# f429ig.net
KiCad netlist of a schematic drawn in Altium Designer
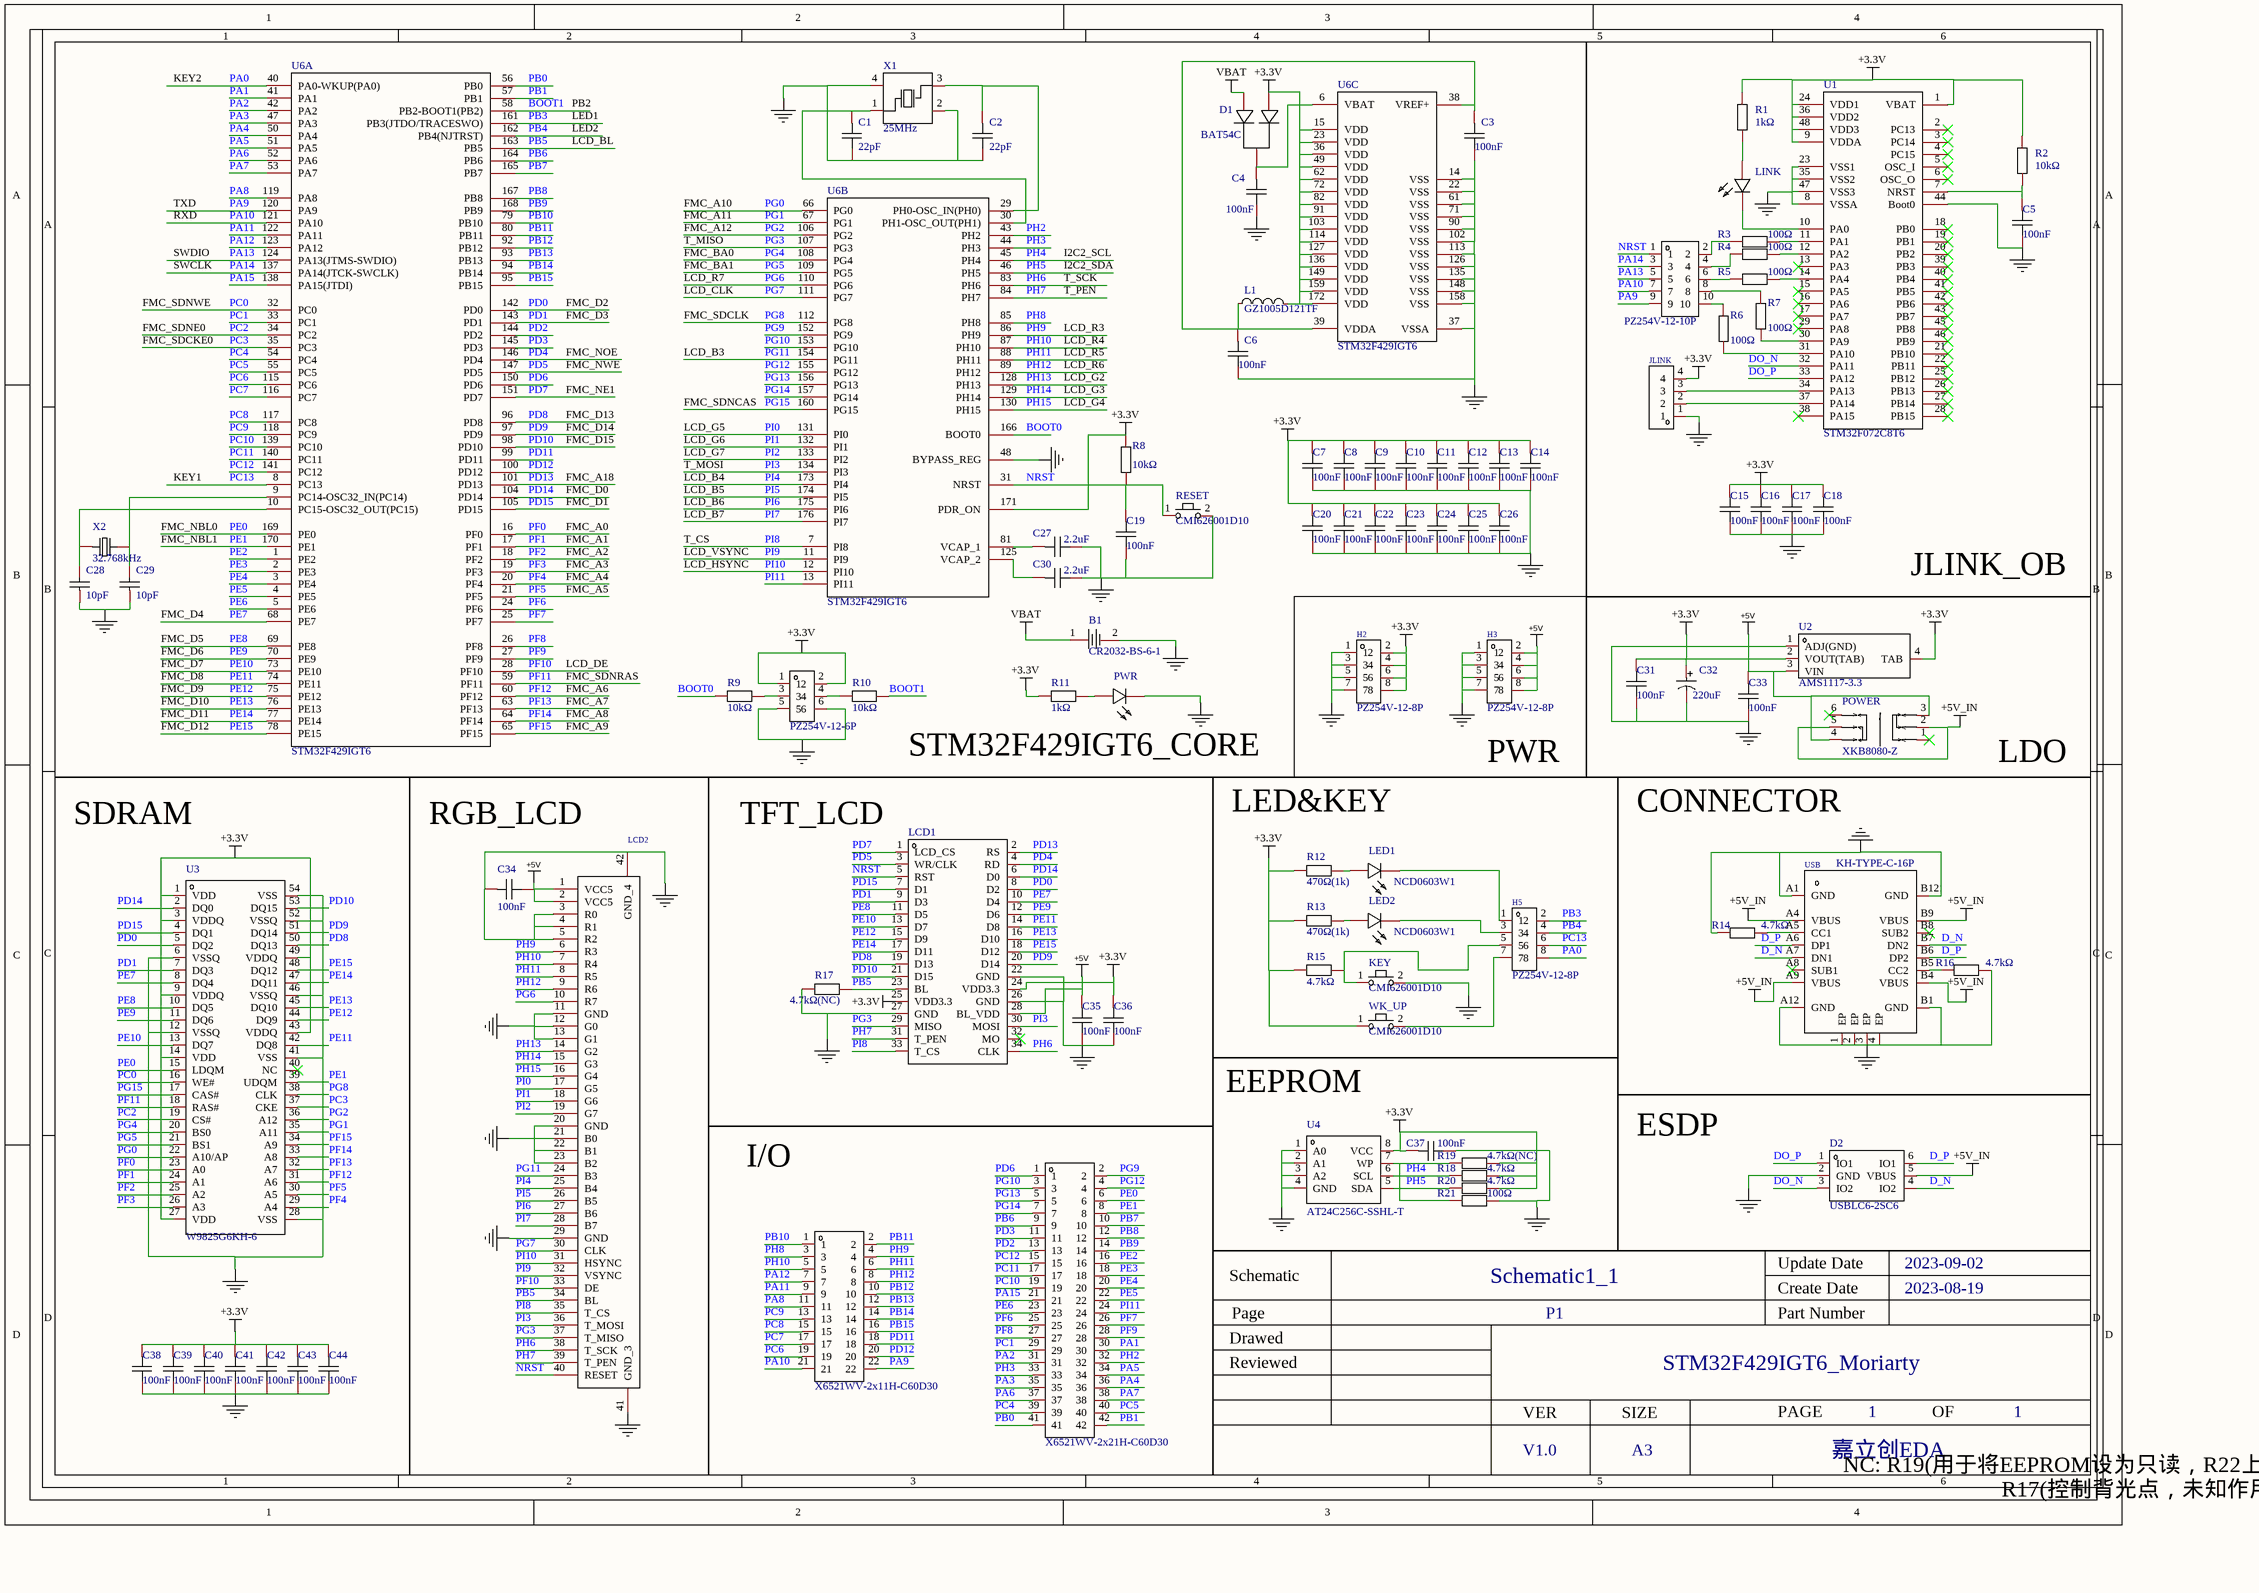
[diagram p0: f429ig.schdoc]

(export (version "E")
  (design (tool "Eeschema 10.0.6"))
  (components
    (comp (ref "B1")
      (value "CR2032-BS-6-1")
      (description "连接器类型:电池底座;适用电池规格:CR2032;工作温度范围:-;")
      (fields (field (name "NAME") "CR2032-BS-6-1") (field (name "MANUFACTURER") "QJ"))
      (libsource (lib "altium-import") (part "root_0_CR2032-BS-6-1_"))
    )
    (comp (ref "C1")
      (value "22pF")
      (description "温度系数:C0G;精度:±5%;额定电压:50V;容值:22pF;")
      (fields
        (field (name "NAME") "22pF")
        (field (name "MANUFACTURER") "FH(风华)")
        (field (name "MANUFACTURER PART") "0603CG220J500NT")
      )
      (libsource (lib "altium-import") (part "root_1_0603CG220J500NT_"))
    )
    (comp (ref "C2")
      (value "22pF")
      (description "温度系数:C0G;精度:±5%;额定电压:50V;容值:22pF;")
      (fields
        (field (name "NAME") "22pF")
        (field (name "MANUFACTURER") "FH(风华)")
        (field (name "MANUFACTURER PART") "0603CG220J500NT")
      )
      (libsource (lib "altium-import") (part "root_1_0603CG220J500NT_"))
    )
    (comp (ref "C3")
      (value "100nF")
      (fields (field (name "NAME") "100nF"))
      (libsource (lib "altium-import") (part "root_1_CAP_0603_"))
    )
    (comp (ref "C4")
      (value "100nF")
      (description "容值:100nF;精度:±10%;额定电压:50V;材质(温度系数):X7R;")
      (fields
        (field (name "NAME") "100nF")
        (field (name "MANUFACTURER") "YAGEO(国巨)")
        (field (name "MANUFACTURER PART") "CC0603KRX7R9BB104")
      )
      (libsource (lib "altium-import") (part "root_1_CC0603KRX7R9BB104_"))
    )
    (comp (ref "C5")
      (value "100nF")
      (description "容值:100nF;精度:±10%;额定电压:50V;材质(温度系数):X7R;")
      (fields
        (field (name "NAME") "100nF")
        (field (name "MANUFACTURER") "YAGEO(国巨)")
        (field (name "MANUFACTURER PART") "CC0603KRX7R9BB104")
      )
      (libsource (lib "altium-import") (part "root_1_CC0603KRX7R9BB104_"))
    )
    (comp (ref "C6")
      (value "100nF")
      (fields (field (name "NAME") "100nF"))
      (libsource (lib "altium-import") (part "root_1_CAP_0603_"))
    )
    (comp (ref "C7")
      (value "100nF")
      (description "容值:100nF;精度:±10%;额定电压:50V;材质(温度系数):X7R;")
      (fields
        (field (name "NAME") "100nF")
        (field (name "MANUFACTURER") "YAGEO(国巨)")
        (field (name "MANUFACTURER PART") "CC0603KRX7R9BB104")
      )
      (libsource (lib "altium-import") (part "root_1_CC0603KRX7R9BB104_"))
    )
    (comp (ref "C8")
      (value "100nF")
      (description "容值:100nF;精度:±10%;额定电压:50V;材质(温度系数):X7R;")
      (fields
        (field (name "NAME") "100nF")
        (field (name "MANUFACTURER") "YAGEO(国巨)")
        (field (name "MANUFACTURER PART") "CC0603KRX7R9BB104")
      )
      (libsource (lib "altium-import") (part "root_1_CC0603KRX7R9BB104_"))
    )
    (comp (ref "C9")
      (value "100nF")
      (description "容值:100nF;精度:±10%;额定电压:50V;材质(温度系数):X7R;")
      (fields
        (field (name "NAME") "100nF")
        (field (name "MANUFACTURER") "YAGEO(国巨)")
        (field (name "MANUFACTURER PART") "CC0603KRX7R9BB104")
      )
      (libsource (lib "altium-import") (part "root_1_CC0603KRX7R9BB104_"))
    )
    (comp (ref "C10")
      (value "100nF")
      (description "容值:100nF;精度:±10%;额定电压:50V;材质(温度系数):X7R;")
      (fields
        (field (name "NAME") "100nF")
        (field (name "MANUFACTURER") "YAGEO(国巨)")
        (field (name "MANUFACTURER PART") "CC0603KRX7R9BB104")
      )
      (libsource (lib "altium-import") (part "root_1_CC0603KRX7R9BB104_"))
    )
    (comp (ref "C11")
      (value "100nF")
      (description "容值:100nF;精度:±10%;额定电压:50V;材质(温度系数):X7R;")
      (fields
        (field (name "NAME") "100nF")
        (field (name "MANUFACTURER") "YAGEO(国巨)")
        (field (name "MANUFACTURER PART") "CC0603KRX7R9BB104")
      )
      (libsource (lib "altium-import") (part "root_1_CC0603KRX7R9BB104_"))
    )
    (comp (ref "C12")
      (value "100nF")
      (description "容值:100nF;精度:±10%;额定电压:50V;材质(温度系数):X7R;")
      (fields
        (field (name "NAME") "100nF")
        (field (name "MANUFACTURER") "YAGEO(国巨)")
        (field (name "MANUFACTURER PART") "CC0603KRX7R9BB104")
      )
      (libsource (lib "altium-import") (part "root_1_CC0603KRX7R9BB104_"))
    )
    (comp (ref "C13")
      (value "100nF")
      (description "容值:100nF;精度:±10%;额定电压:50V;材质(温度系数):X7R;")
      (fields
        (field (name "NAME") "100nF")
        (field (name "MANUFACTURER") "YAGEO(国巨)")
        (field (name "MANUFACTURER PART") "CC0603KRX7R9BB104")
      )
      (libsource (lib "altium-import") (part "root_1_CC0603KRX7R9BB104_"))
    )
    (comp (ref "C14")
      (value "100nF")
      (description "容值:100nF;精度:±10%;额定电压:50V;材质(温度系数):X7R;")
      (fields
        (field (name "NAME") "100nF")
        (field (name "MANUFACTURER") "YAGEO(国巨)")
        (field (name "MANUFACTURER PART") "CC0603KRX7R9BB104")
      )
      (libsource (lib "altium-import") (part "root_1_CC0603KRX7R9BB104_"))
    )
    (comp (ref "C15")
      (value "100nF")
      (description "容值:100nF;精度:±10%;额定电压:50V;材质(温度系数):X7R;")
      (fields
        (field (name "NAME") "100nF")
        (field (name "MANUFACTURER") "YAGEO(国巨)")
        (field (name "MANUFACTURER PART") "CC0603KRX7R9BB104")
      )
      (libsource (lib "altium-import") (part "root_1_CC0603KRX7R9BB104_"))
    )
    (comp (ref "C16")
      (value "100nF")
      (description "容值:100nF;精度:±10%;额定电压:50V;材质(温度系数):X7R;")
      (fields
        (field (name "NAME") "100nF")
        (field (name "MANUFACTURER") "YAGEO(国巨)")
        (field (name "MANUFACTURER PART") "CC0603KRX7R9BB104")
      )
      (libsource (lib "altium-import") (part "root_1_CC0603KRX7R9BB104_"))
    )
    (comp (ref "C17")
      (value "100nF")
      (description "容值:100nF;精度:±10%;额定电压:50V;材质(温度系数):X7R;")
      (fields
        (field (name "NAME") "100nF")
        (field (name "MANUFACTURER") "YAGEO(国巨)")
        (field (name "MANUFACTURER PART") "CC0603KRX7R9BB104")
      )
      (libsource (lib "altium-import") (part "root_1_CC0603KRX7R9BB104_"))
    )
    (comp (ref "C18")
      (value "100nF")
      (description "容值:100nF;精度:±10%;额定电压:50V;材质(温度系数):X7R;")
      (fields
        (field (name "NAME") "100nF")
        (field (name "MANUFACTURER") "YAGEO(国巨)")
        (field (name "MANUFACTURER PART") "CC0603KRX7R9BB104")
      )
      (libsource (lib "altium-import") (part "root_1_CC0603KRX7R9BB104_"))
    )
    (comp (ref "C19")
      (value "100nF")
      (description "容值:100nF;精度:±10%;额定电压:50V;材质(温度系数):X7R;")
      (fields
        (field (name "NAME") "100nF")
        (field (name "MANUFACTURER") "YAGEO(国巨)")
        (field (name "MANUFACTURER PART") "CC0603KRX7R9BB104")
      )
      (libsource (lib "altium-import") (part "root_1_CC0603KRX7R9BB104_"))
    )
    (comp (ref "C20")
      (value "100nF")
      (description "容值:100nF;精度:±10%;额定电压:50V;材质(温度系数):X7R;")
      (fields
        (field (name "NAME") "100nF")
        (field (name "MANUFACTURER") "YAGEO(国巨)")
        (field (name "MANUFACTURER PART") "CC0603KRX7R9BB104")
      )
      (libsource (lib "altium-import") (part "root_1_CC0603KRX7R9BB104_"))
    )
    (comp (ref "C21")
      (value "100nF")
      (description "容值:100nF;精度:±10%;额定电压:50V;材质(温度系数):X7R;")
      (fields
        (field (name "NAME") "100nF")
        (field (name "MANUFACTURER") "YAGEO(国巨)")
        (field (name "MANUFACTURER PART") "CC0603KRX7R9BB104")
      )
      (libsource (lib "altium-import") (part "root_1_CC0603KRX7R9BB104_"))
    )
    (comp (ref "C22")
      (value "100nF")
      (description "容值:100nF;精度:±10%;额定电压:50V;材质(温度系数):X7R;")
      (fields
        (field (name "NAME") "100nF")
        (field (name "MANUFACTURER") "YAGEO(国巨)")
        (field (name "MANUFACTURER PART") "CC0603KRX7R9BB104")
      )
      (libsource (lib "altium-import") (part "root_1_CC0603KRX7R9BB104_"))
    )
    (comp (ref "C23")
      (value "100nF")
      (description "容值:100nF;精度:±10%;额定电压:50V;材质(温度系数):X7R;")
      (fields
        (field (name "NAME") "100nF")
        (field (name "MANUFACTURER") "YAGEO(国巨)")
        (field (name "MANUFACTURER PART") "CC0603KRX7R9BB104")
      )
      (libsource (lib "altium-import") (part "root_1_CC0603KRX7R9BB104_"))
    )
    (comp (ref "C24")
      (value "100nF")
      (description "容值:100nF;精度:±10%;额定电压:50V;材质(温度系数):X7R;")
      (fields
        (field (name "NAME") "100nF")
        (field (name "MANUFACTURER") "YAGEO(国巨)")
        (field (name "MANUFACTURER PART") "CC0603KRX7R9BB104")
      )
      (libsource (lib "altium-import") (part "root_1_CC0603KRX7R9BB104_"))
    )
    (comp (ref "C25")
      (value "100nF")
      (description "容值:100nF;精度:±10%;额定电压:50V;材质(温度系数):X7R;")
      (fields
        (field (name "NAME") "100nF")
        (field (name "MANUFACTURER") "YAGEO(国巨)")
        (field (name "MANUFACTURER PART") "CC0603KRX7R9BB104")
      )
      (libsource (lib "altium-import") (part "root_1_CC0603KRX7R9BB104_"))
    )
    (comp (ref "C26")
      (value "100nF")
      (description "容值:100nF;精度:±10%;额定电压:50V;材质(温度系数):X7R;")
      (fields
        (field (name "NAME") "100nF")
        (field (name "MANUFACTURER") "YAGEO(国巨)")
        (field (name "MANUFACTURER PART") "CC0603KRX7R9BB104")
      )
      (libsource (lib "altium-import") (part "root_1_CC0603KRX7R9BB104_"))
    )
    (comp (ref "C27")
      (value "2.2uF")
      (description "容值:2.2uF;精度:±10%;额定电压:6.3V;材质(温度系数):X5R;")
      (fields
        (field (name "NAME") "2.2uF")
        (field (name "MANUFACTURER") "SAMSUNG(三星)")
        (field (name "MANUFACTURER PART") "CL10A225KQ8NNNC")
      )
      (libsource (lib "altium-import") (part "root_1_CL10A225KQ8NNNC_"))
    )
    (comp (ref "C28")
      (value "10pF")
      (description "容值:10pF;精度:±5%;额定电压:50V;材质(温度系数):NP0;")
      (fields
        (field (name "NAME") "10pF")
        (field (name "MANUFACTURER") "YAGEO(国巨)")
        (field (name "MANUFACTURER PART") "CC0603JRNPO9BN100")
      )
      (libsource (lib "altium-import") (part "root_1_CC0603JRNPO9BN100_"))
    )
    (comp (ref "C29")
      (value "10pF")
      (description "容值:10pF;精度:±5%;额定电压:50V;材质(温度系数):NP0;")
      (fields
        (field (name "NAME") "10pF")
        (field (name "MANUFACTURER") "YAGEO(国巨)")
        (field (name "MANUFACTURER PART") "CC0603JRNPO9BN100")
      )
      (libsource (lib "altium-import") (part "root_1_CC0603JRNPO9BN100_"))
    )
    (comp (ref "C30")
      (value "2.2uF")
      (description "容值:2.2uF;精度:±10%;额定电压:6.3V;材质(温度系数):X5R;")
      (fields
        (field (name "NAME") "2.2uF")
        (field (name "MANUFACTURER") "SAMSUNG(三星)")
        (field (name "MANUFACTURER PART") "CL10A225KQ8NNNC")
      )
      (libsource (lib "altium-import") (part "root_1_CL10A225KQ8NNNC_"))
    )
    (comp (ref "C31")
      (value "100nF")
      (description "容值:100nF;精度:±10%;额定电压:50V;材质(温度系数):X7R;")
      (fields
        (field (name "NAME") "100nF")
        (field (name "MANUFACTURER") "YAGEO(国巨)")
        (field (name "MANUFACTURER PART") "CC0603KRX7R9BB104")
      )
      (libsource (lib "altium-import") (part "root_1_CC0603KRX7R9BB104_"))
    )
    (comp (ref "C32")
      (value "220uF")
      (description "容值:220uF;精度:±20%;额定电压:10V;纹波电流:-;等效串联电阻:-;")
      (fields
        (field (name "NAME") "220uF")
        (field (name "MANUFACTURER") "ROQANG(容强)")
        (field (name "MANUFACTURER PART") "RVT1A221M0605")
      )
      (libsource (lib "altium-import") (part "root_0_RVT1A221M0605_C72494_"))
    )
    (comp (ref "C33")
      (value "100nF")
      (description "容值:100nF;精度:±10%;额定电压:50V;材质(温度系数):X7R;")
      (fields
        (field (name "NAME") "100nF")
        (field (name "MANUFACTURER") "YAGEO(国巨)")
        (field (name "MANUFACTURER PART") "CC0603KRX7R9BB104")
      )
      (libsource (lib "altium-import") (part "root_1_CC0603KRX7R9BB104_"))
    )
    (comp (ref "C34")
      (value "100nF")
      (description "容值:100nF;精度:±10%;额定电压:50V;材质(温度系数):X7R;")
      (fields
        (field (name "NAME") "100nF")
        (field (name "MANUFACTURER") "YAGEO(国巨)")
        (field (name "MANUFACTURER PART") "CC0603KRX7R9BB104")
      )
      (libsource (lib "altium-import") (part "root_2_CC0603KRX7R9BB104_"))
    )
    (comp (ref "C35")
      (value "100nF")
      (description "容值:100nF;精度:±10%;额定电压:50V;材质(温度系数):X7R;")
      (fields
        (field (name "NAME") "100nF")
        (field (name "MANUFACTURER") "YAGEO(国巨)")
        (field (name "MANUFACTURER PART") "CC0603KRX7R9BB104")
      )
      (libsource (lib "altium-import") (part "root_1_CC0603KRX7R9BB104_"))
    )
    (comp (ref "C36")
      (value "100nF")
      (description "容值:100nF;精度:±10%;额定电压:50V;材质(温度系数):X7R;")
      (fields
        (field (name "NAME") "100nF")
        (field (name "MANUFACTURER") "YAGEO(国巨)")
        (field (name "MANUFACTURER PART") "CC0603KRX7R9BB104")
      )
      (libsource (lib "altium-import") (part "root_1_CC0603KRX7R9BB104_"))
    )
    (comp (ref "C37")
      (value "100nF")
      (description "容值:100nF;精度:±10%;额定电压:50V;材质(温度系数):X7R;")
      (fields
        (field (name "NAME") "100nF")
        (field (name "MANUFACTURER") "YAGEO(国巨)")
        (field (name "MANUFACTURER PART") "CC0603KRX7R9BB104")
      )
      (libsource (lib "altium-import") (part "root_2_CC0603KRX7R9BB104_"))
    )
    (comp (ref "C38")
      (value "100nF")
      (description "容值:100nF;精度:±10%;额定电压:50V;材质(温度系数):X7R;")
      (fields
        (field (name "NAME") "100nF")
        (field (name "MANUFACTURER") "YAGEO(国巨)")
        (field (name "MANUFACTURER PART") "CC0603KRX7R9BB104")
      )
      (libsource (lib "altium-import") (part "root_1_CC0603KRX7R9BB104_"))
    )
    (comp (ref "C39")
      (value "100nF")
      (description "容值:100nF;精度:±10%;额定电压:50V;材质(温度系数):X7R;")
      (fields
        (field (name "NAME") "100nF")
        (field (name "MANUFACTURER") "YAGEO(国巨)")
        (field (name "MANUFACTURER PART") "CC0603KRX7R9BB104")
      )
      (libsource (lib "altium-import") (part "root_1_CC0603KRX7R9BB104_"))
    )
    (comp (ref "C40")
      (value "100nF")
      (description "容值:100nF;精度:±10%;额定电压:50V;材质(温度系数):X7R;")
      (fields
        (field (name "NAME") "100nF")
        (field (name "MANUFACTURER") "YAGEO(国巨)")
        (field (name "MANUFACTURER PART") "CC0603KRX7R9BB104")
      )
      (libsource (lib "altium-import") (part "root_1_CC0603KRX7R9BB104_"))
    )
    (comp (ref "C41")
      (value "100nF")
      (description "容值:100nF;精度:±10%;额定电压:50V;材质(温度系数):X7R;")
      (fields
        (field (name "NAME") "100nF")
        (field (name "MANUFACTURER") "YAGEO(国巨)")
        (field (name "MANUFACTURER PART") "CC0603KRX7R9BB104")
      )
      (libsource (lib "altium-import") (part "root_1_CC0603KRX7R9BB104_"))
    )
    (comp (ref "C42")
      (value "100nF")
      (description "容值:100nF;精度:±10%;额定电压:50V;材质(温度系数):X7R;")
      (fields
        (field (name "NAME") "100nF")
        (field (name "MANUFACTURER") "YAGEO(国巨)")
        (field (name "MANUFACTURER PART") "CC0603KRX7R9BB104")
      )
      (libsource (lib "altium-import") (part "root_1_CC0603KRX7R9BB104_"))
    )
    (comp (ref "C43")
      (value "100nF")
      (description "容值:100nF;精度:±10%;额定电压:50V;材质(温度系数):X7R;")
      (fields
        (field (name "NAME") "100nF")
        (field (name "MANUFACTURER") "YAGEO(国巨)")
        (field (name "MANUFACTURER PART") "CC0603KRX7R9BB104")
      )
      (libsource (lib "altium-import") (part "root_1_CC0603KRX7R9BB104_"))
    )
    (comp (ref "C44")
      (value "100nF")
      (description "容值:100nF;精度:±10%;额定电压:50V;材质(温度系数):X7R;")
      (fields
        (field (name "NAME") "100nF")
        (field (name "MANUFACTURER") "YAGEO(国巨)")
        (field (name "MANUFACTURER PART") "CC0603KRX7R9BB104")
      )
      (libsource (lib "altium-import") (part "root_1_CC0603KRX7R9BB104_"))
    )
    (comp (ref "D1")
      (value "BAT54C")
      (description "二极管配置:-;直流反向耐压(Vr):30V;平均整流电流(Io):200mA;正向压降(Vf):1V@100mA;")
      (fields (field (name "NAME") "BAT54C") (field (name "MANUFACTURER") "CJ(江苏长电/长晶)"))
      (libsource (lib "altium-import") (part "root_3_BAT54C_C2135_"))
    )
    (comp (ref "D2")
      (value "USBLC6-2SC6")
      (description "USBLC6-2SC6 Vrwm:5V 印记：UL26  ESD静电管静电放电(ESD)保护器件")
      (fields (field (name "NAME") "USBLC6-2SC6") (field (name "MANUFACTURER") "TECH PUBLIC(台舟)"))
      (libsource (lib "altium-import") (part "root_0_USBLC6-2SC6_C2827654_"))
    )
    (comp (ref "H1")
      (value "PZ254V-12-10P")
      (fields (field (name "NAME") "PZ254V-12-10P") (field (name "MANUFACTURER") "XFCN(兴飞)"))
      (libsource (lib "altium-import") (part "root_0_PZ254V-12-10P_"))
    )
    (comp (ref "H2")
      (value "PZ254V-12-8P")
      (fields (field (name "NAME") "PZ254V-12-8P") (field (name "MANUFACTURER") "XFCN(兴飞)"))
      (libsource (lib "altium-import") (part "root_0_PZ254V-12-8P_"))
    )
    (comp (ref "H3")
      (value "PZ254V-12-8P")
      (fields (field (name "NAME") "PZ254V-12-8P") (field (name "MANUFACTURER") "XFCN(兴飞)"))
      (libsource (lib "altium-import") (part "root_0_PZ254V-12-8P_"))
    )
    (comp (ref "H4")
      (value "PZ254V-12-6P")
      (fields (field (name "NAME") "PZ254V-12-6P") (field (name "MANUFACTURER") "XFCN(兴飞)"))
      (libsource (lib "altium-import") (part "root_0_PZ254V-12-6P_"))
    )
    (comp (ref "H5")
      (value "PZ254V-12-8P")
      (fields (field (name "NAME") "PZ254V-12-8P") (field (name "MANUFACTURER") "XFCN(兴飞)"))
      (libsource (lib "altium-import") (part "root_0_PZ254V-12-8P_"))
    )
    (comp (ref "H6")
      (value "X6521WV-2x11H-C60D30")
      (fields
        (field (name "NAME") "X6521WV-2x11H-C60D30")
        (field (name "MANUFACTURER") "XKB Connectivity(中国星坤)")
      )
      (libsource (lib "altium-import") (part "root_0_X6521WV-2x11H-C60D30_"))
    )
    (comp (ref "JLINK")
      (value "PZ254V-11-04P")
      (fields (field (name "MANUFACTURER") "XFCN(兴飞)"))
      (libsource (lib "altium-import") (part "root_2_PZ254V-11-04P_"))
    )
    (comp (ref "KEY")
      (value "CMI626001D10")
      (fields (field (name "NAME") "CMI626001D10") (field (name "MANUFACTURER") "Kailh(凯华)"))
      (libsource (lib "altium-import") (part "root_0_CMI626001D10_"))
    )
    (comp (ref "L1")
      (value "GZ1005D121TF")
      (description "标称阻抗@测试频率:120Ω@100MHz;误差:±25%;直流电阻(RDC):400mΩ;")
      (fields
        (field (name "NAME") "GZ1005D121TF")
        (field (name "MANUFACTURER") "Sunlord(顺络)")
        (field (name "TOLERANCE") "±25%")
      )
      (libsource (lib "altium-import") (part "root_0_GZ1005D121TF_"))
    )
    (comp (ref "LCD1") (value "~") (libsource (lib "altium-import") (part "root_0_PM2.54-2*17_")))
    (comp (ref "LCD2") (value "~") (libsource (lib "altium-import") (part "root_0_AFC01-S40FCA-00_")))
    (comp (ref "LED1")
      (value "NCD0603W1")
      (description "发光颜色:白灯;")
      (fields (field (name "NAME") "NCD0603W1") (field (name "MANUFACTURER") "国星光电"))
      (libsource (lib "altium-import") (part "root_2_NCD0603W1_"))
    )
    (comp (ref "LED2")
      (value "NCD0603W1")
      (description "发光颜色:白灯;")
      (fields (field (name "NAME") "NCD0603W1") (field (name "MANUFACTURER") "国星光电"))
      (libsource (lib "altium-import") (part "root_2_NCD0603W1_"))
    )
    (comp (ref "LINK")
      (value "NCD0603W1")
      (description "发光颜色:白灯;")
      (fields (field (name "MANUFACTURER") "国星光电"))
      (libsource (lib "altium-import") (part "root_1_NCD0603W1_"))
    )
    (comp (ref "POWER")
      (value "XKB8080-Z")
      (fields (field (name "NAME") "XKB8080-Z") (field (name "MANUFACTURER") "XKB Connectivity(中国星坤)"))
      (libsource (lib "altium-import") (part "root_1_XKB8080-Z_"))
    )
    (comp (ref "PWR")
      (value "NCD0603W1")
      (description "发光颜色:白灯;")
      (fields (field (name "MANUFACTURER") "国星光电"))
      (libsource (lib "altium-import") (part "root_2_NCD0603W1_"))
    )
    (comp (ref "R1")
      (value "1kΩ")
      (description "电阻类型:厚膜电阻;阻值:1kΩ;精度:±1%;功率:100mW;")
      (fields
        (field (name "NAME") "1kΩ")
        (field (name "MANUFACTURER") "UNI-ROYAL(厚声)")
        (field (name "MANUFACTURER PART") "0603WAF1001T5E")
      )
      (libsource (lib "altium-import") (part "root_1_0603WAF1001T5E_"))
    )
    (comp (ref "R2")
      (value "10kΩ")
      (description "电阻类型:厚膜电阻;阻值:10kΩ;精度:±1%;功率:100mW;")
      (fields
        (field (name "NAME") "10kΩ")
        (field (name "MANUFACTURER") "UNI-ROYAL(厚声)")
        (field (name "MANUFACTURER PART") "0603WAF1002T5E")
      )
      (libsource (lib "altium-import") (part "root_1_0603WAF1002T5E_"))
    )
    (comp (ref "R3")
      (value "100Ω")
      (description "电阻类型:厚膜电阻;阻值:100Ω;精度:±1%;功率:100mW;")
      (fields
        (field (name "NAME") "100Ω")
        (field (name "MANUFACTURER") "UNI-ROYAL(厚声)")
        (field (name "MANUFACTURER PART") "0603WAF1000T5E")
      )
      (libsource (lib "altium-import") (part "root_2_0603WAF1000T5E_"))
    )
    (comp (ref "R4")
      (value "100Ω")
      (description "电阻类型:厚膜电阻;阻值:100Ω;精度:±1%;功率:100mW;")
      (fields
        (field (name "NAME") "100Ω")
        (field (name "MANUFACTURER") "UNI-ROYAL(厚声)")
        (field (name "MANUFACTURER PART") "0603WAF1000T5E")
      )
      (libsource (lib "altium-import") (part "root_2_0603WAF1000T5E_"))
    )
    (comp (ref "R5")
      (value "100Ω")
      (description "电阻类型:厚膜电阻;阻值:100Ω;精度:±1%;功率:100mW;")
      (fields
        (field (name "NAME") "100Ω")
        (field (name "MANUFACTURER") "UNI-ROYAL(厚声)")
        (field (name "MANUFACTURER PART") "0603WAF1000T5E")
      )
      (libsource (lib "altium-import") (part "root_2_0603WAF1000T5E_"))
    )
    (comp (ref "R6")
      (value "100Ω")
      (description "电阻类型:厚膜电阻;阻值:100Ω;精度:±1%;功率:100mW;")
      (fields
        (field (name "NAME") "100Ω")
        (field (name "MANUFACTURER") "UNI-ROYAL(厚声)")
        (field (name "MANUFACTURER PART") "0603WAF1000T5E")
      )
      (libsource (lib "altium-import") (part "root_3_0603WAF1000T5E_"))
    )
    (comp (ref "R7")
      (value "100Ω")
      (description "电阻类型:厚膜电阻;阻值:100Ω;精度:±1%;功率:100mW;")
      (fields
        (field (name "NAME") "100Ω")
        (field (name "MANUFACTURER") "UNI-ROYAL(厚声)")
        (field (name "MANUFACTURER PART") "0603WAF1000T5E")
      )
      (libsource (lib "altium-import") (part "root_3_0603WAF1000T5E_"))
    )
    (comp (ref "R8")
      (value "10kΩ")
      (description "电阻类型:厚膜电阻;阻值:10kΩ;精度:±1%;功率:100mW;")
      (fields
        (field (name "NAME") "10kΩ")
        (field (name "MANUFACTURER") "UNI-ROYAL(厚声)")
        (field (name "MANUFACTURER PART") "0603WAF1002T5E")
      )
      (libsource (lib "altium-import") (part "root_1_0603WAF1002T5E_"))
    )
    (comp (ref "R9")
      (value "10kΩ")
      (description "电阻类型:厚膜电阻;阻值:10kΩ;精度:±1%;功率:100mW;")
      (fields
        (field (name "NAME") "10kΩ")
        (field (name "MANUFACTURER") "UNI-ROYAL(厚声)")
        (field (name "MANUFACTURER PART") "0603WAF1002T5E")
      )
      (libsource (lib "altium-import") (part "root_2_0603WAF1002T5E_"))
    )
    (comp (ref "R10")
      (value "10kΩ")
      (description "电阻类型:厚膜电阻;阻值:10kΩ;精度:±1%;功率:100mW;")
      (fields
        (field (name "NAME") "10kΩ")
        (field (name "MANUFACTURER") "UNI-ROYAL(厚声)")
        (field (name "MANUFACTURER PART") "0603WAF1002T5E")
      )
      (libsource (lib "altium-import") (part "root_2_0603WAF1002T5E_"))
    )
    (comp (ref "R11")
      (value "1kΩ")
      (description "电阻类型:厚膜电阻;阻值:1kΩ;精度:±1%;功率:100mW;")
      (fields
        (field (name "NAME") "1kΩ")
        (field (name "MANUFACTURER") "UNI-ROYAL(厚声)")
        (field (name "MANUFACTURER PART") "0603WAF1001T5E")
      )
      (libsource (lib "altium-import") (part "root_2_0603WAF1001T5E_"))
    )
    (comp (ref "R12")
      (value "470Ω(1k)")
      (description "电阻类型:厚膜电阻;阻值:470Ω;精度:±1%;功率:100mW;")
      (fields
        (field (name "NAME") "470Ω(1k)")
        (field (name "MANUFACTURER") "UNI-ROYAL(厚声)")
        (field (name "MANUFACTURER PART") "0603WAF4700T5E")
      )
      (libsource (lib "altium-import") (part "root_0_0603WAF4700T5E_"))
    )
    (comp (ref "R13")
      (value "470Ω(1k)")
      (description "电阻类型:厚膜电阻;阻值:470Ω;精度:±1%;功率:100mW;")
      (fields
        (field (name "NAME") "470Ω(1k)")
        (field (name "MANUFACTURER") "UNI-ROYAL(厚声)")
        (field (name "MANUFACTURER PART") "0603WAF4700T5E")
      )
      (libsource (lib "altium-import") (part "root_0_0603WAF4700T5E_"))
    )
    (comp (ref "R14")
      (value "4.7kΩ")
      (description "电阻类型:厚膜电阻;阻值:4.7kΩ;精度:±1%;功率:100mW;")
      (fields
        (field (name "NAME") "4.7kΩ")
        (field (name "MANUFACTURER") "UNI-ROYAL(厚声)")
        (field (name "MANUFACTURER PART") "0603WAF4701T5E")
      )
      (libsource (lib "altium-import") (part "root_2_0603WAF4701T5E_"))
    )
    (comp (ref "R15")
      (value "4.7kΩ")
      (description "电阻类型:厚膜电阻;阻值:4.7kΩ;精度:±1%;功率:100mW;")
      (fields
        (field (name "NAME") "4.7kΩ")
        (field (name "MANUFACTURER") "UNI-ROYAL(厚声)")
        (field (name "MANUFACTURER PART") "0603WAF4701T5E")
      )
      (libsource (lib "altium-import") (part "root_2_0603WAF4701T5E_"))
    )
    (comp (ref "R16")
      (value "4.7kΩ")
      (description "电阻类型:厚膜电阻;阻值:4.7kΩ;精度:±1%;功率:100mW;")
      (fields
        (field (name "NAME") "4.7kΩ")
        (field (name "MANUFACTURER") "UNI-ROYAL(厚声)")
        (field (name "MANUFACTURER PART") "0603WAF4701T5E")
      )
      (libsource (lib "altium-import") (part "root_2_0603WAF4701T5E_"))
    )
    (comp (ref "R17")
      (value "4.7kΩ(NC)")
      (description "电阻类型:厚膜电阻;阻值:4.7kΩ;精度:±1%;功率:100mW;")
      (fields
        (field (name "NAME") "4.7kΩ(NC)")
        (field (name "MANUFACTURER") "UNI-ROYAL(厚声)")
        (field (name "MANUFACTURER PART") "0603WAF4701T5E")
      )
      (libsource (lib "altium-import") (part "root_2_0603WAF4701T5E_"))
    )
    (comp (ref "R18")
      (value "4.7kΩ")
      (description "电阻类型:厚膜电阻;阻值:4.7kΩ;精度:±1%;功率:100mW;")
      (fields
        (field (name "NAME") "4.7kΩ")
        (field (name "MANUFACTURER") "UNI-ROYAL(厚声)")
        (field (name "MANUFACTURER PART") "0603WAF4701T5E")
      )
      (libsource (lib "altium-import") (part "root_2_0603WAF4701T5E_"))
    )
    (comp (ref "R19")
      (value "4.7kΩ(NC)")
      (description "电阻类型:厚膜电阻;阻值:4.7kΩ;精度:±1%;功率:100mW;")
      (fields
        (field (name "NAME") "4.7kΩ(NC)")
        (field (name "MANUFACTURER") "UNI-ROYAL(厚声)")
        (field (name "MANUFACTURER PART") "0603WAF4701T5E")
      )
      (libsource (lib "altium-import") (part "root_2_0603WAF4701T5E_"))
    )
    (comp (ref "R20")
      (value "4.7kΩ")
      (description "电阻类型:厚膜电阻;阻值:4.7kΩ;精度:±1%;功率:100mW;")
      (fields
        (field (name "NAME") "4.7kΩ")
        (field (name "MANUFACTURER") "UNI-ROYAL(厚声)")
        (field (name "MANUFACTURER PART") "0603WAF4701T5E")
      )
      (libsource (lib "altium-import") (part "root_2_0603WAF4701T5E_"))
    )
    (comp (ref "R21")
      (value "100Ω")
      (description "电阻类型:厚膜电阻;阻值:100Ω;精度:±1%;功率:100mW;")
      (fields
        (field (name "NAME") "100Ω")
        (field (name "MANUFACTURER") "UNI-ROYAL(厚声)")
        (field (name "MANUFACTURER PART") "0603WAF1000T5E")
      )
      (libsource (lib "altium-import") (part "root_2_0603WAF1000T5E_"))
    )
    (comp (ref "RESET")
      (value "CMI626001D10")
      (fields (field (name "NAME") "CMI626001D10") (field (name "MANUFACTURER") "Kailh(凯华)"))
      (libsource (lib "altium-import") (part "root_0_CMI626001D10_"))
    )
    (comp (ref "U1")
      (value "STM32F072C8T6")
      (fields (field (name "NAME") "STM32F072C8T6") (field (name "MANUFACTURER") "ST(意法半导体)"))
      (libsource (lib "altium-import") (part "root_0_STM32F072C8T6_"))
    )
    (comp (ref "U2")
      (value "AMS1117-3.3")
      (description "输出类型:固定;输出极性:正;最大输入电压:18V;输出电压:3.3V;输出电流:1A;电源纹波抑制比(PSRR):60dB@(120Hz);")
      (fields (field (name "NAME") "AMS1117-3.3") (field (name "MANUFACTURER") "UMW(广东友台半导体)"))
      (libsource (lib "altium-import") (part "root_0_AMS1117-3.3_C347222_"))
    )
    (comp (ref "U3")
      (value "W9825G6KH-6")
      (fields (field (name "NAME") "W9825G6KH-6") (field (name "MANUFACTURER") "WINBOND(华邦)"))
      (libsource (lib "altium-import") (part "root_0_W9825G6KH-6_"))
    )
    (comp (ref "U4")
      (value "AT24C256C-SSHL-T")
      (fields (field (name "NAME") "AT24C256C-SSHL-T") (field (name "MANUFACTURER") "MICROCHIP(美国微芯)"))
      (libsource (lib "altium-import") (part "root_0_AT24C256C-SSHL-T_"))
    )
    (comp (ref "U5")
      (value "X6521WV-2x21H-C60D30")
      (fields
        (field (name "NAME") "X6521WV-2x21H-C60D30")
        (field (name "MANUFACTURER") "XKB Connectivity(中国星坤)")
      )
      (libsource (lib "altium-import") (part "root_0_X6521WV-2x21H-C60D30_"))
    )
    (comp (ref "U6")
      (value "STM32F429IGT6")
      (description "CPU内核:ARM Cortex-M4;CPU最大主频:180MHz;程序存储容量:1MB;程序存储器类型:FLASH;RAM总容量:256KB;GPIO端口数量:140;")
      (fields (field (name "NAME") "STM32F429IGT6") (field (name "MANUFACTURER") "ST(意法半导体)"))
      (libsource (lib "altium-import") (part "root_0_STM32F429IGT6_"))
    )
    (comp (ref "USB")
      (value "KH-TYPE-C-16P")
      (description "Type-C母座 16PIN 立式四角贴板无压片")
      (fields (field (name "NAME") "KH-TYPE-C-16P") (field (name "MANUFACTURER") "kinghelm(金航标)"))
      (libsource (lib "altium-import") (part "root_0_KH-TYPE-C-16P_"))
    )
    (comp (ref "WK_UP")
      (value "CMI626001D10")
      (fields (field (name "NAME") "CMI626001D10") (field (name "MANUFACTURER") "Kailh(凯华)"))
      (libsource (lib "altium-import") (part "root_0_CMI626001D10_"))
    )
    (comp (ref "X1")
      (value "25MHz")
      (description "频率:25MHz;频率公差:±10ppm;负载电容:12pF;")
      (fields
        (field (name "NAME") "25MHz")
        (field (name "MANUFACTURER") "YXC(扬兴晶振)")
        (field (name "MANUFACTURER PART") "X322525MOB4SI")
      )
      (libsource (lib "altium-import") (part "root_0_X322525MOB4SI_"))
    )
    (comp (ref "X2")
      (value "32.768kHz")
      (description "频率:32.768kHz;频率公差:±20ppm;负载电容:6pF;")
      (fields
        (field (name "NAME") "32.768kHz")
        (field (name "MANUFACTURER") "EPSON(爱普生)")
        (field (name "MANUFACTURER PART") "Q13FC1350004900")
      )
      (libsource (lib "altium-import") (part "root_0_Q13FC1350004900_"))
    )
  )
  (nets
    (net (code "1") (name "+3.3V") (class "Default")
      (node (ref "C10") (pin "2") (pinfunction "2_2") (pintype "passive"))
      (node (ref "C11") (pin "2") (pinfunction "2_2") (pintype "passive"))
      (node (ref "C12") (pin "2") (pinfunction "2_2") (pintype "passive"))
      (node (ref "C13") (pin "2") (pinfunction "2_2") (pintype "passive"))
      (node (ref "C14") (pin "2") (pinfunction "2_2") (pintype "passive"))
      (node (ref "C15") (pin "2") (pinfunction "2_2") (pintype "passive"))
      (node (ref "C16") (pin "2") (pinfunction "2_2") (pintype "passive"))
      (node (ref "C17") (pin "2") (pinfunction "2_2") (pintype "passive"))
      (node (ref "C18") (pin "2") (pinfunction "2_2") (pintype "passive"))
      (node (ref "C20") (pin "2") (pinfunction "2_2") (pintype "passive"))
      (node (ref "C21") (pin "2") (pinfunction "2_2") (pintype "passive"))
      (node (ref "C22") (pin "2") (pinfunction "2_2") (pintype "passive"))
      (node (ref "C23") (pin "2") (pinfunction "2_2") (pintype "passive"))
      (node (ref "C24") (pin "2") (pinfunction "2_2") (pintype "passive"))
      (node (ref "C25") (pin "2") (pinfunction "2_2") (pintype "passive"))
      (node (ref "C26") (pin "2") (pinfunction "2_2") (pintype "passive"))
      (node (ref "C31") (pin "2") (pinfunction "2_2") (pintype "passive"))
      (node (ref "C32") (pin "1") (pinfunction "1_1") (pintype "passive"))
      (node (ref "C36") (pin "2") (pinfunction "2_2") (pintype "passive"))
      (node (ref "C37") (pin "2") (pinfunction "2_2") (pintype "passive"))
      (node (ref "C38") (pin "2") (pinfunction "2_2") (pintype "passive"))
      (node (ref "C39") (pin "2") (pinfunction "2_2") (pintype "passive"))
      (node (ref "C40") (pin "2") (pinfunction "2_2") (pintype "passive"))
      (node (ref "C41") (pin "2") (pinfunction "2_2") (pintype "passive"))
      (node (ref "C42") (pin "2") (pinfunction "2_2") (pintype "passive"))
      (node (ref "C43") (pin "2") (pinfunction "2_2") (pintype "passive"))
      (node (ref "C44") (pin "2") (pinfunction "2_2") (pintype "passive"))
      (node (ref "C7") (pin "2") (pinfunction "2_2") (pintype "passive"))
      (node (ref "C8") (pin "2") (pinfunction "2_2") (pintype "passive"))
      (node (ref "C9") (pin "2") (pinfunction "2_2") (pintype "passive"))
      (node (ref "D1") (pin "1") (pinfunction "A1_1") (pintype "passive"))
      (node (ref "H2") (pin "2") (pinfunction "2_2") (pintype "passive"))
      (node (ref "H2") (pin "4") (pinfunction "4_4") (pintype "passive"))
      (node (ref "H2") (pin "6") (pinfunction "6_6") (pintype "passive"))
      (node (ref "H2") (pin "8") (pinfunction "8_8") (pintype "passive"))
      (node (ref "H4") (pin "1") (pinfunction "1_1") (pintype "passive"))
      (node (ref "H4") (pin "2") (pinfunction "2_2") (pintype "passive"))
      (node (ref "JLINK") (pin "4") (pinfunction "4_4") (pintype "passive"))
      (node (ref "L1") (pin "2") (pinfunction "2_2") (pintype "passive"))
      (node (ref "LCD1") (pin "24") (pinfunction "VDD3.3_24") (pintype "passive"))
      (node (ref "LCD1") (pin "25") (pinfunction "VDD3.3_25") (pintype "passive"))
      (node (ref "R1") (pin "2") (pinfunction "2_2") (pintype "passive"))
      (node (ref "R11") (pin "2") (pinfunction "2_2") (pintype "passive"))
      (node (ref "R12") (pin "1") (pinfunction "1_1") (pintype "passive"))
      (node (ref "R13") (pin "1") (pinfunction "1_1") (pintype "passive"))
      (node (ref "R15") (pin "2") (pinfunction "2_2") (pintype "passive"))
      (node (ref "R18") (pin "1") (pinfunction "1_1") (pintype "passive"))
      (node (ref "R19") (pin "1") (pinfunction "1_1") (pintype "passive"))
      (node (ref "R2") (pin "2") (pinfunction "2_2") (pintype "passive"))
      (node (ref "R20") (pin "1") (pinfunction "1_1") (pintype "passive"))
      (node (ref "R8") (pin "2") (pinfunction "2_2") (pintype "passive"))
      (node (ref "U1") (pin "1") (pinfunction "VBAT_1") (pintype "passive"))
      (node (ref "U1") (pin "24") (pinfunction "VDD1_24") (pintype "passive"))
      (node (ref "U1") (pin "36") (pinfunction "VDD2_36") (pintype "passive"))
      (node (ref "U1") (pin "48") (pinfunction "VDD3_48") (pintype "passive"))
      (node (ref "U1") (pin "9") (pinfunction "VDDA_9") (pintype "passive"))
      (node (ref "U2") (pin "2") (pinfunction "VOUT(TAB)_2") (pintype "passive"))
      (node (ref "U2") (pin "4") (pinfunction "TAB_4") (pintype "passive"))
      (node (ref "U3") (pin "1") (pinfunction "VDD_1") (pintype "passive"))
      (node (ref "U3") (pin "14") (pinfunction "VDD_14") (pintype "passive"))
      (node (ref "U3") (pin "27") (pinfunction "VDD_27") (pintype "passive"))
      (node (ref "U3") (pin "3") (pinfunction "VDDQ_3") (pintype "passive"))
      (node (ref "U3") (pin "43") (pinfunction "VDDQ_43") (pintype "passive"))
      (node (ref "U3") (pin "49") (pinfunction "VDDQ_49") (pintype "passive"))
      (node (ref "U3") (pin "9") (pinfunction "VDDQ_9") (pintype "passive"))
      (node (ref "U4") (pin "8") (pinfunction "VCC_8") (pintype "passive"))
      (node (ref "U6") (pin "103") (pinfunction "VDD_103") (pintype "passive"))
      (node (ref "U6") (pin "114") (pinfunction "VDD_114") (pintype "passive"))
      (node (ref "U6") (pin "127") (pinfunction "VDD_127") (pintype "passive"))
      (node (ref "U6") (pin "136") (pinfunction "VDD_136") (pintype "passive"))
      (node (ref "U6") (pin "149") (pinfunction "VDD_149") (pintype "passive"))
      (node (ref "U6") (pin "15") (pinfunction "VDD_15") (pintype "passive"))
      (node (ref "U6") (pin "159") (pinfunction "VDD_159") (pintype "passive"))
      (node (ref "U6") (pin "171") (pinfunction "PDR_ON_171") (pintype "passive"))
      (node (ref "U6") (pin "172") (pinfunction "VDD_172") (pintype "passive"))
      (node (ref "U6") (pin "23") (pinfunction "VDD_23") (pintype "passive"))
      (node (ref "U6") (pin "36") (pinfunction "VDD_36") (pintype "passive"))
      (node (ref "U6") (pin "49") (pinfunction "VDD_49") (pintype "passive"))
      (node (ref "U6") (pin "62") (pinfunction "VDD_62") (pintype "passive"))
      (node (ref "U6") (pin "72") (pinfunction "VDD_72") (pintype "passive"))
      (node (ref "U6") (pin "82") (pinfunction "VDD_82") (pintype "passive"))
      (node (ref "U6") (pin "91") (pinfunction "VDD_91") (pintype "passive"))
      (node (ref "WK_UP") (pin "1") (pinfunction "1_1") (pintype "passive"))
    )
    (net (code "2") (name "+5V") (class "Default")
      (node (ref "C33") (pin "2") (pinfunction "2_2") (pintype "passive"))
      (node (ref "C34") (pin "1") (pinfunction "1_1") (pintype "passive"))
      (node (ref "C35") (pin "2") (pinfunction "2_2") (pintype "passive"))
      (node (ref "H3") (pin "2") (pinfunction "2_2") (pintype "passive"))
      (node (ref "H3") (pin "4") (pinfunction "4_4") (pintype "passive"))
      (node (ref "H3") (pin "6") (pinfunction "6_6") (pintype "passive"))
      (node (ref "H3") (pin "8") (pinfunction "8_8") (pintype "passive"))
      (node (ref "LCD1") (pin "28") (pinfunction "BL_VDD_28") (pintype "passive"))
      (node (ref "LCD2") (pin "1") (pinfunction "VCC5_1") (pintype "passive"))
      (node (ref "LCD2") (pin "2") (pinfunction "VCC5_2") (pintype "passive"))
      (node (ref "POWER") (pin "3") (pinfunction "3_3") (pintype "passive"))
      (node (ref "POWER") (pin "4") (pinfunction "4_4") (pintype "passive"))
      (node (ref "U2") (pin "3") (pinfunction "VIN_3") (pintype "passive"))
    )
    (net (code "3") (name "+5V_IN") (class "Default")
      (node (ref "D2") (pin "5") (pinfunction "VBUS_5") (pintype "passive"))
      (node (ref "POWER") (pin "2") (pinfunction "2_2") (pintype "passive"))
      (node (ref "POWER") (pin "5") (pinfunction "5_5") (pintype "passive"))
      (node (ref "USB") (pin "A4") (pinfunction "VBUS_A4") (pintype "passive"))
      (node (ref "USB") (pin "A9") (pinfunction "VBUS_A9") (pintype "passive"))
      (node (ref "USB") (pin "B4") (pinfunction "VBUS_B4") (pintype "passive"))
      (node (ref "USB") (pin "B9") (pinfunction "VBUS_B9") (pintype "passive"))
    )
    (net (code "4") (name "/BOOT0") (class "Default")
      (node (ref "R9") (pin "2") (pinfunction "2_2") (pintype "passive"))
      (node (ref "U6") (pin "166") (pinfunction "BOOT0_166") (pintype "passive"))
    )
    (net (code "5") (name "/BOOT1") (class "Default")
      (node (ref "R10") (pin "1") (pinfunction "1_1") (pintype "passive"))
      (node (ref "U6") (pin "58") (pinfunction "PB2-BOOT1(PB2)_58") (pintype "passive"))
    )
    (net (code "6") (name "/DO_N") (class "Default")
      (node (ref "D2") (pin "3") (pinfunction "IO2_3") (pintype "passive"))
      (node (ref "U1") (pin "32") (pinfunction "PA11_32") (pintype "passive"))
    )
    (net (code "7") (name "/DO_P") (class "Default")
      (node (ref "D2") (pin "1") (pinfunction "IO1_1") (pintype "passive"))
      (node (ref "U1") (pin "33") (pinfunction "PA12_33") (pintype "passive"))
    )
    (net (code "8") (name "/D_N") (class "Default")
      (node (ref "D2") (pin "4") (pinfunction "IO2_4") (pintype "passive"))
      (node (ref "USB") (pin "A7") (pinfunction "DN1_A7") (pintype "passive"))
      (node (ref "USB") (pin "B7") (pinfunction "DN2_B7") (pintype "passive"))
    )
    (net (code "9") (name "/D_P") (class "Default")
      (node (ref "D2") (pin "6") (pinfunction "IO1_6") (pintype "passive"))
      (node (ref "USB") (pin "A6") (pinfunction "DP1_A6") (pintype "passive"))
      (node (ref "USB") (pin "B6") (pinfunction "DP2_B6") (pintype "passive"))
    )
    (net (code "10") (name "/NRST") (class "Default")
      (node (ref "C19") (pin "2") (pinfunction "2_2") (pintype "passive"))
      (node (ref "H1") (pin "1") (pinfunction "1_1") (pintype "passive"))
      (node (ref "LCD1") (pin "5") (pinfunction "RST_5") (pintype "passive"))
      (node (ref "LCD2") (pin "40") (pinfunction "RESET_40") (pintype "passive"))
      (node (ref "R8") (pin "1") (pinfunction "1_1") (pintype "passive"))
      (node (ref "RESET") (pin "1") (pinfunction "1_1") (pintype "passive"))
      (node (ref "U6") (pin "31") (pinfunction "NRST_31") (pintype "passive"))
    )
    (net (code "11") (name "/PA0") (class "Default")
      (node (ref "H5") (pin "8") (pinfunction "8_8") (pintype "passive"))
      (node (ref "U6") (pin "40") (pinfunction "PA0-WKUP(PA0)_40") (pintype "passive"))
    )
    (net (code "12") (name "/PA1") (class "Default")
      (node (ref "U5") (pin "30") (pinfunction "30_30") (pintype "passive"))
      (node (ref "U6") (pin "41") (pinfunction "PA1_41") (pintype "passive"))
    )
    (net (code "13") (name "/PA2") (class "Default")
      (node (ref "U5") (pin "31") (pinfunction "31_31") (pintype "passive"))
      (node (ref "U6") (pin "42") (pinfunction "PA2_42") (pintype "passive"))
    )
    (net (code "14") (name "/PA3") (class "Default")
      (node (ref "U5") (pin "35") (pinfunction "35_35") (pintype "passive"))
      (node (ref "U6") (pin "47") (pinfunction "PA3_47") (pintype "passive"))
    )
    (net (code "15") (name "/PA4") (class "Default")
      (node (ref "U5") (pin "36") (pinfunction "36_36") (pintype "passive"))
      (node (ref "U6") (pin "50") (pinfunction "PA4_50") (pintype "passive"))
    )
    (net (code "16") (name "/PA5") (class "Default")
      (node (ref "U5") (pin "34") (pinfunction "34_34") (pintype "passive"))
      (node (ref "U6") (pin "51") (pinfunction "PA5_51") (pintype "passive"))
    )
    (net (code "17") (name "/PA6") (class "Default")
      (node (ref "U5") (pin "37") (pinfunction "37_37") (pintype "passive"))
      (node (ref "U6") (pin "52") (pinfunction "PA6_52") (pintype "passive"))
    )
    (net (code "18") (name "/PA7") (class "Default")
      (node (ref "U5") (pin "38") (pinfunction "38_38") (pintype "passive"))
      (node (ref "U6") (pin "53") (pinfunction "PA7_53") (pintype "passive"))
    )
    (net (code "19") (name "/PA8") (class "Default")
      (node (ref "H6") (pin "11") (pinfunction "11_11") (pintype "passive"))
      (node (ref "U6") (pin "119") (pinfunction "PA8_119") (pintype "passive"))
    )
    (net (code "20") (name "/PA9") (class "Default")
      (node (ref "H1") (pin "9") (pinfunction "9_9") (pintype "passive"))
      (node (ref "H6") (pin "22") (pinfunction "22_22") (pintype "passive"))
      (node (ref "U6") (pin "120") (pinfunction "PA9_120") (pintype "passive"))
    )
    (net (code "21") (name "/PA10") (class "Default")
      (node (ref "H1") (pin "7") (pinfunction "7_7") (pintype "passive"))
      (node (ref "H6") (pin "21") (pinfunction "21_21") (pintype "passive"))
      (node (ref "U6") (pin "121") (pinfunction "PA10_121") (pintype "passive"))
    )
    (net (code "22") (name "/PA11") (class "Default")
      (node (ref "H6") (pin "9") (pinfunction "9_9") (pintype "passive"))
      (node (ref "U6") (pin "122") (pinfunction "PA11_122") (pintype "passive"))
    )
    (net (code "23") (name "/PA12") (class "Default")
      (node (ref "H6") (pin "7") (pinfunction "7_7") (pintype "passive"))
      (node (ref "U6") (pin "123") (pinfunction "PA12_123") (pintype "passive"))
    )
    (net (code "24") (name "/PA13") (class "Default")
      (node (ref "H1") (pin "5") (pinfunction "5_5") (pintype "passive"))
      (node (ref "U6") (pin "124") (pinfunction "PA13(JTMS-SWDIO)_124") (pintype "passive"))
    )
    (net (code "25") (name "/PA14") (class "Default")
      (node (ref "H1") (pin "3") (pinfunction "3_3") (pintype "passive"))
      (node (ref "U6") (pin "137") (pinfunction "PA14(JTCK-SWCLK)_137") (pintype "passive"))
    )
    (net (code "26") (name "/PA15") (class "Default")
      (node (ref "U5") (pin "21") (pinfunction "21_21") (pintype "passive"))
      (node (ref "U6") (pin "138") (pinfunction "PA15(JTDI)_138") (pintype "passive"))
    )
    (net (code "27") (name "/PB0") (class "Default")
      (node (ref "U5") (pin "41") (pinfunction "41_41") (pintype "passive"))
      (node (ref "U6") (pin "56") (pinfunction "PB0_56") (pintype "passive"))
    )
    (net (code "28") (name "/PB1") (class "Default")
      (node (ref "U5") (pin "42") (pinfunction "42_42") (pintype "passive"))
      (node (ref "U6") (pin "57") (pinfunction "PB1_57") (pintype "passive"))
    )
    (net (code "29") (name "/PB3") (class "Default")
      (node (ref "H5") (pin "2") (pinfunction "2_2") (pintype "passive"))
      (node (ref "U6") (pin "161") (pinfunction "PB3(JTDO/TRACESWO)_161") (pintype "passive"))
    )
    (net (code "30") (name "/PB4") (class "Default")
      (node (ref "H5") (pin "4") (pinfunction "4_4") (pintype "passive"))
      (node (ref "U6") (pin "162") (pinfunction "PB4(NJTRST)_162") (pintype "passive"))
    )
    (net (code "31") (name "/PB5") (class "Default")
      (node (ref "LCD1") (pin "23") (pinfunction "BL_23") (pintype "passive"))
      (node (ref "LCD2") (pin "34") (pinfunction "BL_34") (pintype "passive"))
      (node (ref "R17") (pin "1") (pinfunction "1_1") (pintype "passive"))
      (node (ref "U6") (pin "163") (pinfunction "PB5_163") (pintype "passive"))
    )
    (net (code "32") (name "/PB6") (class "Default")
      (node (ref "U5") (pin "9") (pinfunction "9_9") (pintype "passive"))
      (node (ref "U6") (pin "164") (pinfunction "PB6_164") (pintype "passive"))
    )
    (net (code "33") (name "/PB7") (class "Default")
      (node (ref "U5") (pin "10") (pinfunction "10_10") (pintype "passive"))
      (node (ref "U6") (pin "165") (pinfunction "PB7_165") (pintype "passive"))
    )
    (net (code "34") (name "/PB8") (class "Default")
      (node (ref "U5") (pin "12") (pinfunction "12_12") (pintype "passive"))
      (node (ref "U6") (pin "167") (pinfunction "PB8_167") (pintype "passive"))
    )
    (net (code "35") (name "/PB9") (class "Default")
      (node (ref "U5") (pin "14") (pinfunction "14_14") (pintype "passive"))
      (node (ref "U6") (pin "168") (pinfunction "PB9_168") (pintype "passive"))
    )
    (net (code "36") (name "/PB10") (class "Default")
      (node (ref "H6") (pin "1") (pinfunction "1_1") (pintype "passive"))
      (node (ref "U6") (pin "79") (pinfunction "PB10_79") (pintype "passive"))
    )
    (net (code "37") (name "/PB11") (class "Default")
      (node (ref "H6") (pin "2") (pinfunction "2_2") (pintype "passive"))
      (node (ref "U6") (pin "80") (pinfunction "PB11_80") (pintype "passive"))
    )
    (net (code "38") (name "/PB12") (class "Default")
      (node (ref "H6") (pin "10") (pinfunction "10_10") (pintype "passive"))
      (node (ref "U6") (pin "92") (pinfunction "PB12_92") (pintype "passive"))
    )
    (net (code "39") (name "/PB13") (class "Default")
      (node (ref "H6") (pin "12") (pinfunction "12_12") (pintype "passive"))
      (node (ref "U6") (pin "93") (pinfunction "PB13_93") (pintype "passive"))
    )
    (net (code "40") (name "/PB14") (class "Default")
      (node (ref "H6") (pin "14") (pinfunction "14_14") (pintype "passive"))
      (node (ref "U6") (pin "94") (pinfunction "PB14_94") (pintype "passive"))
    )
    (net (code "41") (name "/PB15") (class "Default")
      (node (ref "H6") (pin "16") (pinfunction "16_16") (pintype "passive"))
      (node (ref "U6") (pin "95") (pinfunction "PB15_95") (pintype "passive"))
    )
    (net (code "42") (name "/PC0") (class "Default")
      (node (ref "U3") (pin "16") (pinfunction "WE#_16") (pintype "passive"))
      (node (ref "U6") (pin "32") (pinfunction "PC0_32") (pintype "passive"))
    )
    (net (code "43") (name "/PC1") (class "Default")
      (node (ref "U5") (pin "29") (pinfunction "29_29") (pintype "passive"))
      (node (ref "U6") (pin "33") (pinfunction "PC1_33") (pintype "passive"))
    )
    (net (code "44") (name "/PC2") (class "Default")
      (node (ref "U3") (pin "19") (pinfunction "CS#_19") (pintype "passive"))
      (node (ref "U6") (pin "34") (pinfunction "PC2_34") (pintype "passive"))
    )
    (net (code "45") (name "/PC3") (class "Default")
      (node (ref "U3") (pin "37") (pinfunction "CKE_37") (pintype "passive"))
      (node (ref "U6") (pin "35") (pinfunction "PC3_35") (pintype "passive"))
    )
    (net (code "46") (name "/PC4") (class "Default")
      (node (ref "U5") (pin "39") (pinfunction "39_39") (pintype "passive"))
      (node (ref "U6") (pin "54") (pinfunction "PC4_54") (pintype "passive"))
    )
    (net (code "47") (name "/PC5") (class "Default")
      (node (ref "U5") (pin "40") (pinfunction "40_40") (pintype "passive"))
      (node (ref "U6") (pin "55") (pinfunction "PC5_55") (pintype "passive"))
    )
    (net (code "48") (name "/PC6") (class "Default")
      (node (ref "H6") (pin "19") (pinfunction "19_19") (pintype "passive"))
      (node (ref "U6") (pin "115") (pinfunction "PC6_115") (pintype "passive"))
    )
    (net (code "49") (name "/PC7") (class "Default")
      (node (ref "H6") (pin "17") (pinfunction "17_17") (pintype "passive"))
      (node (ref "U6") (pin "116") (pinfunction "PC7_116") (pintype "passive"))
    )
    (net (code "50") (name "/PC8") (class "Default")
      (node (ref "H6") (pin "15") (pinfunction "15_15") (pintype "passive"))
      (node (ref "U6") (pin "117") (pinfunction "PC8_117") (pintype "passive"))
    )
    (net (code "51") (name "/PC9") (class "Default")
      (node (ref "H6") (pin "13") (pinfunction "13_13") (pintype "passive"))
      (node (ref "U6") (pin "118") (pinfunction "PC9_118") (pintype "passive"))
    )
    (net (code "52") (name "/PC10") (class "Default")
      (node (ref "U5") (pin "19") (pinfunction "19_19") (pintype "passive"))
      (node (ref "U6") (pin "139") (pinfunction "PC10_139") (pintype "passive"))
    )
    (net (code "53") (name "/PC11") (class "Default")
      (node (ref "U5") (pin "17") (pinfunction "17_17") (pintype "passive"))
      (node (ref "U6") (pin "140") (pinfunction "PC11_140") (pintype "passive"))
    )
    (net (code "54") (name "/PC12") (class "Default")
      (node (ref "U5") (pin "15") (pinfunction "15_15") (pintype "passive"))
      (node (ref "U6") (pin "141") (pinfunction "PC12_141") (pintype "passive"))
    )
    (net (code "55") (name "/PC13") (class "Default")
      (node (ref "H5") (pin "6") (pinfunction "6_6") (pintype "passive"))
      (node (ref "U6") (pin "8") (pinfunction "PC13_8") (pintype "passive"))
    )
    (net (code "56") (name "/PD0") (class "Default")
      (node (ref "LCD1") (pin "8") (pinfunction "D2_8") (pintype "passive"))
      (node (ref "U3") (pin "5") (pinfunction "DQ2_5") (pintype "passive"))
      (node (ref "U6") (pin "142") (pinfunction "PD0_142") (pintype "passive"))
    )
    (net (code "57") (name "/PD1") (class "Default")
      (node (ref "LCD1") (pin "9") (pinfunction "D3_9") (pintype "passive"))
      (node (ref "U3") (pin "7") (pinfunction "DQ3_7") (pintype "passive"))
      (node (ref "U6") (pin "143") (pinfunction "PD1_143") (pintype "passive"))
    )
    (net (code "58") (name "/PD2") (class "Default")
      (node (ref "U5") (pin "13") (pinfunction "13_13") (pintype "passive"))
      (node (ref "U6") (pin "144") (pinfunction "PD2_144") (pintype "passive"))
    )
    (net (code "59") (name "/PD3") (class "Default")
      (node (ref "U5") (pin "11") (pinfunction "11_11") (pintype "passive"))
      (node (ref "U6") (pin "145") (pinfunction "PD3_145") (pintype "passive"))
    )
    (net (code "60") (name "/PD4") (class "Default")
      (node (ref "LCD1") (pin "4") (pinfunction "RD_4") (pintype "passive"))
      (node (ref "U6") (pin "146") (pinfunction "PD4_146") (pintype "passive"))
    )
    (net (code "61") (name "/PD5") (class "Default")
      (node (ref "LCD1") (pin "3") (pinfunction "WR/CLK_3") (pintype "passive"))
      (node (ref "U6") (pin "147") (pinfunction "PD5_147") (pintype "passive"))
    )
    (net (code "62") (name "/PD6") (class "Default")
      (node (ref "U5") (pin "1") (pinfunction "1_1") (pintype "passive"))
      (node (ref "U6") (pin "150") (pinfunction "PD6_150") (pintype "passive"))
    )
    (net (code "63") (name "/PD7") (class "Default")
      (node (ref "LCD1") (pin "1") (pinfunction "LCD_CS_1") (pintype "passive"))
      (node (ref "U6") (pin "151") (pinfunction "PD7_151") (pintype "passive"))
    )
    (net (code "64") (name "/PD8") (class "Default")
      (node (ref "LCD1") (pin "19") (pinfunction "D13_19") (pintype "passive"))
      (node (ref "U3") (pin "50") (pinfunction "DQ13_50") (pintype "passive"))
      (node (ref "U6") (pin "96") (pinfunction "PD8_96") (pintype "passive"))
    )
    (net (code "65") (name "/PD9") (class "Default")
      (node (ref "LCD1") (pin "20") (pinfunction "D14_20") (pintype "passive"))
      (node (ref "U3") (pin "51") (pinfunction "DQ14_51") (pintype "passive"))
      (node (ref "U6") (pin "97") (pinfunction "PD9_97") (pintype "passive"))
    )
    (net (code "66") (name "/PD10") (class "Default")
      (node (ref "LCD1") (pin "21") (pinfunction "D15_21") (pintype "passive"))
      (node (ref "U3") (pin "53") (pinfunction "DQ15_53") (pintype "passive"))
      (node (ref "U6") (pin "98") (pinfunction "PD10_98") (pintype "passive"))
    )
    (net (code "67") (name "/PD11") (class "Default")
      (node (ref "H6") (pin "18") (pinfunction "18_18") (pintype "passive"))
      (node (ref "U6") (pin "99") (pinfunction "PD11_99") (pintype "passive"))
    )
    (net (code "68") (name "/PD12") (class "Default")
      (node (ref "H6") (pin "20") (pinfunction "20_20") (pintype "passive"))
      (node (ref "U6") (pin "100") (pinfunction "PD12_100") (pintype "passive"))
    )
    (net (code "69") (name "/PD13") (class "Default")
      (node (ref "LCD1") (pin "2") (pinfunction "RS_2") (pintype "passive"))
      (node (ref "U6") (pin "101") (pinfunction "PD13_101") (pintype "passive"))
    )
    (net (code "70") (name "/PD14") (class "Default")
      (node (ref "LCD1") (pin "6") (pinfunction "D0_6") (pintype "passive"))
      (node (ref "U3") (pin "2") (pinfunction "DQ0_2") (pintype "passive"))
      (node (ref "U6") (pin "104") (pinfunction "PD14_104") (pintype "passive"))
    )
    (net (code "71") (name "/PD15") (class "Default")
      (node (ref "LCD1") (pin "7") (pinfunction "D1_7") (pintype "passive"))
      (node (ref "U3") (pin "4") (pinfunction "DQ1_4") (pintype "passive"))
      (node (ref "U6") (pin "105") (pinfunction "PD15_105") (pintype "passive"))
    )
    (net (code "72") (name "/PE0") (class "Default")
      (node (ref "U3") (pin "15") (pinfunction "LDQM_15") (pintype "passive"))
      (node (ref "U5") (pin "6") (pinfunction "6_6") (pintype "passive"))
      (node (ref "U6") (pin "169") (pinfunction "PE0_169") (pintype "passive"))
    )
    (net (code "73") (name "/PE1") (class "Default")
      (node (ref "U3") (pin "39") (pinfunction "UDQM_39") (pintype "passive"))
      (node (ref "U5") (pin "8") (pinfunction "8_8") (pintype "passive"))
      (node (ref "U6") (pin "170") (pinfunction "PE1_170") (pintype "passive"))
    )
    (net (code "74") (name "/PE2") (class "Default")
      (node (ref "U5") (pin "16") (pinfunction "16_16") (pintype "passive"))
      (node (ref "U6") (pin "1") (pinfunction "PE2_1") (pintype "passive"))
    )
    (net (code "75") (name "/PE3") (class "Default")
      (node (ref "U5") (pin "18") (pinfunction "18_18") (pintype "passive"))
      (node (ref "U6") (pin "2") (pinfunction "PE3_2") (pintype "passive"))
    )
    (net (code "76") (name "/PE4") (class "Default")
      (node (ref "U5") (pin "20") (pinfunction "20_20") (pintype "passive"))
      (node (ref "U6") (pin "3") (pinfunction "PE4_3") (pintype "passive"))
    )
    (net (code "77") (name "/PE5") (class "Default")
      (node (ref "U5") (pin "22") (pinfunction "22_22") (pintype "passive"))
      (node (ref "U6") (pin "4") (pinfunction "PE5_4") (pintype "passive"))
    )
    (net (code "78") (name "/PE6") (class "Default")
      (node (ref "U5") (pin "23") (pinfunction "23_23") (pintype "passive"))
      (node (ref "U6") (pin "5") (pinfunction "PE6_5") (pintype "passive"))
    )
    (net (code "79") (name "/PE7") (class "Default")
      (node (ref "LCD1") (pin "10") (pinfunction "D4_10") (pintype "passive"))
      (node (ref "U3") (pin "8") (pinfunction "DQ4_8") (pintype "passive"))
      (node (ref "U6") (pin "68") (pinfunction "PE7_68") (pintype "passive"))
    )
    (net (code "80") (name "/PE8") (class "Default")
      (node (ref "LCD1") (pin "11") (pinfunction "D5_11") (pintype "passive"))
      (node (ref "U3") (pin "10") (pinfunction "DQ5_10") (pintype "passive"))
      (node (ref "U6") (pin "69") (pinfunction "PE8_69") (pintype "passive"))
    )
    (net (code "81") (name "/PE9") (class "Default")
      (node (ref "LCD1") (pin "12") (pinfunction "D6_12") (pintype "passive"))
      (node (ref "U3") (pin "11") (pinfunction "DQ6_11") (pintype "passive"))
      (node (ref "U6") (pin "70") (pinfunction "PE9_70") (pintype "passive"))
    )
    (net (code "82") (name "/PE10") (class "Default")
      (node (ref "LCD1") (pin "13") (pinfunction "D7_13") (pintype "passive"))
      (node (ref "U3") (pin "13") (pinfunction "DQ7_13") (pintype "passive"))
      (node (ref "U6") (pin "73") (pinfunction "PE10_73") (pintype "passive"))
    )
    (net (code "83") (name "/PE11") (class "Default")
      (node (ref "LCD1") (pin "14") (pinfunction "D8_14") (pintype "passive"))
      (node (ref "U3") (pin "42") (pinfunction "DQ8_42") (pintype "passive"))
      (node (ref "U6") (pin "74") (pinfunction "PE11_74") (pintype "passive"))
    )
    (net (code "84") (name "/PE12") (class "Default")
      (node (ref "LCD1") (pin "15") (pinfunction "D9_15") (pintype "passive"))
      (node (ref "U3") (pin "44") (pinfunction "DQ9_44") (pintype "passive"))
      (node (ref "U6") (pin "75") (pinfunction "PE12_75") (pintype "passive"))
    )
    (net (code "85") (name "/PE13") (class "Default")
      (node (ref "LCD1") (pin "16") (pinfunction "D10_16") (pintype "passive"))
      (node (ref "U3") (pin "45") (pinfunction "DQ10_45") (pintype "passive"))
      (node (ref "U6") (pin "76") (pinfunction "PE13_76") (pintype "passive"))
    )
    (net (code "86") (name "/PE14") (class "Default")
      (node (ref "LCD1") (pin "17") (pinfunction "D11_17") (pintype "passive"))
      (node (ref "U3") (pin "47") (pinfunction "DQ11_47") (pintype "passive"))
      (node (ref "U6") (pin "77") (pinfunction "PE14_77") (pintype "passive"))
    )
    (net (code "87") (name "/PE15") (class "Default")
      (node (ref "LCD1") (pin "18") (pinfunction "D12_18") (pintype "passive"))
      (node (ref "U3") (pin "48") (pinfunction "DQ12_48") (pintype "passive"))
      (node (ref "U6") (pin "78") (pinfunction "PE15_78") (pintype "passive"))
    )
    (net (code "88") (name "/PF0") (class "Default")
      (node (ref "U3") (pin "23") (pinfunction "A0_23") (pintype "passive"))
      (node (ref "U6") (pin "16") (pinfunction "PF0_16") (pintype "passive"))
    )
    (net (code "89") (name "/PF1") (class "Default")
      (node (ref "U3") (pin "24") (pinfunction "A1_24") (pintype "passive"))
      (node (ref "U6") (pin "17") (pinfunction "PF1_17") (pintype "passive"))
    )
    (net (code "90") (name "/PF2") (class "Default")
      (node (ref "U3") (pin "25") (pinfunction "A2_25") (pintype "passive"))
      (node (ref "U6") (pin "18") (pinfunction "PF2_18") (pintype "passive"))
    )
    (net (code "91") (name "/PF3") (class "Default")
      (node (ref "U3") (pin "26") (pinfunction "A3_26") (pintype "passive"))
      (node (ref "U6") (pin "19") (pinfunction "PF3_19") (pintype "passive"))
    )
    (net (code "92") (name "/PF4") (class "Default")
      (node (ref "U3") (pin "29") (pinfunction "A4_29") (pintype "passive"))
      (node (ref "U6") (pin "20") (pinfunction "PF4_20") (pintype "passive"))
    )
    (net (code "93") (name "/PF5") (class "Default")
      (node (ref "U3") (pin "30") (pinfunction "A5_30") (pintype "passive"))
      (node (ref "U6") (pin "21") (pinfunction "PF5_21") (pintype "passive"))
    )
    (net (code "94") (name "/PF6") (class "Default")
      (node (ref "U5") (pin "25") (pinfunction "25_25") (pintype "passive"))
      (node (ref "U6") (pin "24") (pinfunction "PF6_24") (pintype "passive"))
    )
    (net (code "95") (name "/PF7") (class "Default")
      (node (ref "U5") (pin "26") (pinfunction "26_26") (pintype "passive"))
      (node (ref "U6") (pin "25") (pinfunction "PF7_25") (pintype "passive"))
    )
    (net (code "96") (name "/PF8") (class "Default")
      (node (ref "U5") (pin "27") (pinfunction "27_27") (pintype "passive"))
      (node (ref "U6") (pin "26") (pinfunction "PF8_26") (pintype "passive"))
    )
    (net (code "97") (name "/PF9") (class "Default")
      (node (ref "U5") (pin "28") (pinfunction "28_28") (pintype "passive"))
      (node (ref "U6") (pin "27") (pinfunction "PF9_27") (pintype "passive"))
    )
    (net (code "98") (name "/PF10") (class "Default")
      (node (ref "LCD2") (pin "33") (pinfunction "DE_33") (pintype "passive"))
      (node (ref "U6") (pin "28") (pinfunction "PF10_28") (pintype "passive"))
    )
    (net (code "99") (name "/PF11") (class "Default")
      (node (ref "U3") (pin "18") (pinfunction "RAS#_18") (pintype "passive"))
      (node (ref "U6") (pin "59") (pinfunction "PF11_59") (pintype "passive"))
    )
    (net (code "100") (name "/PF12") (class "Default")
      (node (ref "U3") (pin "31") (pinfunction "A6_31") (pintype "passive"))
      (node (ref "U6") (pin "60") (pinfunction "PF12_60") (pintype "passive"))
    )
    (net (code "101") (name "/PF13") (class "Default")
      (node (ref "U3") (pin "32") (pinfunction "A7_32") (pintype "passive"))
      (node (ref "U6") (pin "63") (pinfunction "PF13_63") (pintype "passive"))
    )
    (net (code "102") (name "/PF14") (class "Default")
      (node (ref "U3") (pin "33") (pinfunction "A8_33") (pintype "passive"))
      (node (ref "U6") (pin "64") (pinfunction "PF14_64") (pintype "passive"))
    )
    (net (code "103") (name "/PF15") (class "Default")
      (node (ref "U3") (pin "34") (pinfunction "A9_34") (pintype "passive"))
      (node (ref "U6") (pin "65") (pinfunction "PF15_65") (pintype "passive"))
    )
    (net (code "104") (name "/PG0") (class "Default")
      (node (ref "U3") (pin "22") (pinfunction "A10/AP_22") (pintype "passive"))
      (node (ref "U6") (pin "66") (pinfunction "PG0_66") (pintype "passive"))
    )
    (net (code "105") (name "/PG1") (class "Default")
      (node (ref "U3") (pin "35") (pinfunction "A11_35") (pintype "passive"))
      (node (ref "U6") (pin "67") (pinfunction "PG1_67") (pintype "passive"))
    )
    (net (code "106") (name "/PG2") (class "Default")
      (node (ref "U3") (pin "36") (pinfunction "A12_36") (pintype "passive"))
      (node (ref "U6") (pin "106") (pinfunction "PG2_106") (pintype "passive"))
    )
    (net (code "107") (name "/PG3") (class "Default")
      (node (ref "LCD1") (pin "29") (pinfunction "MISO_29") (pintype "passive"))
      (node (ref "LCD2") (pin "37") (pinfunction "T_MISO_37") (pintype "passive"))
      (node (ref "U6") (pin "107") (pinfunction "PG3_107") (pintype "passive"))
    )
    (net (code "108") (name "/PG4") (class "Default")
      (node (ref "U3") (pin "20") (pinfunction "BS0_20") (pintype "passive"))
      (node (ref "U6") (pin "108") (pinfunction "PG4_108") (pintype "passive"))
    )
    (net (code "109") (name "/PG5") (class "Default")
      (node (ref "U3") (pin "21") (pinfunction "BS1_21") (pintype "passive"))
      (node (ref "U6") (pin "109") (pinfunction "PG5_109") (pintype "passive"))
    )
    (net (code "110") (name "/PG6") (class "Default")
      (node (ref "LCD2") (pin "10") (pinfunction "R7_10") (pintype "passive"))
      (node (ref "U6") (pin "110") (pinfunction "PG6_110") (pintype "passive"))
    )
    (net (code "111") (name "/PG7") (class "Default")
      (node (ref "LCD2") (pin "30") (pinfunction "CLK_30") (pintype "passive"))
      (node (ref "U6") (pin "111") (pinfunction "PG7_111") (pintype "passive"))
    )
    (net (code "112") (name "/PG8") (class "Default")
      (node (ref "U3") (pin "38") (pinfunction "CLK_38") (pintype "passive"))
      (node (ref "U6") (pin "112") (pinfunction "PG8_112") (pintype "passive"))
    )
    (net (code "113") (name "/PG9") (class "Default")
      (node (ref "U5") (pin "2") (pinfunction "2_2") (pintype "passive"))
      (node (ref "U6") (pin "152") (pinfunction "PG9_152") (pintype "passive"))
    )
    (net (code "114") (name "/PG10") (class "Default")
      (node (ref "U5") (pin "3") (pinfunction "3_3") (pintype "passive"))
      (node (ref "U6") (pin "153") (pinfunction "PG10_153") (pintype "passive"))
    )
    (net (code "115") (name "/PG11") (class "Default")
      (node (ref "LCD2") (pin "24") (pinfunction "B3_24") (pintype "passive"))
      (node (ref "U6") (pin "154") (pinfunction "PG11_154") (pintype "passive"))
    )
    (net (code "116") (name "/PG12") (class "Default")
      (node (ref "U5") (pin "4") (pinfunction "4_4") (pintype "passive"))
      (node (ref "U6") (pin "155") (pinfunction "PG12_155") (pintype "passive"))
    )
    (net (code "117") (name "/PG13") (class "Default")
      (node (ref "U5") (pin "5") (pinfunction "5_5") (pintype "passive"))
      (node (ref "U6") (pin "156") (pinfunction "PG13_156") (pintype "passive"))
    )
    (net (code "118") (name "/PG14") (class "Default")
      (node (ref "U5") (pin "7") (pinfunction "7_7") (pintype "passive"))
      (node (ref "U6") (pin "157") (pinfunction "PG14_157") (pintype "passive"))
    )
    (net (code "119") (name "/PG15") (class "Default")
      (node (ref "U3") (pin "17") (pinfunction "CAS#_17") (pintype "passive"))
      (node (ref "U6") (pin "160") (pinfunction "PG15_160") (pintype "passive"))
    )
    (net (code "120") (name "/PH2") (class "Default")
      (node (ref "U5") (pin "32") (pinfunction "32_32") (pintype "passive"))
      (node (ref "U6") (pin "43") (pinfunction "PH2_43") (pintype "passive"))
    )
    (net (code "121") (name "/PH3") (class "Default")
      (node (ref "U5") (pin "33") (pinfunction "33_33") (pintype "passive"))
      (node (ref "U6") (pin "44") (pinfunction "PH3_44") (pintype "passive"))
    )
    (net (code "122") (name "/PH4") (class "Default")
      (node (ref "R18") (pin "2") (pinfunction "2_2") (pintype "passive"))
      (node (ref "U4") (pin "6") (pinfunction "SCL_6") (pintype "passive"))
      (node (ref "U6") (pin "45") (pinfunction "PH4_45") (pintype "passive"))
    )
    (net (code "123") (name "/PH5") (class "Default")
      (node (ref "R20") (pin "2") (pinfunction "2_2") (pintype "passive"))
      (node (ref "U4") (pin "5") (pinfunction "SDA_5") (pintype "passive"))
      (node (ref "U6") (pin "46") (pinfunction "PH5_46") (pintype "passive"))
    )
    (net (code "124") (name "/PH6") (class "Default")
      (node (ref "LCD1") (pin "34") (pinfunction "CLK_34") (pintype "passive"))
      (node (ref "LCD2") (pin "38") (pinfunction "T_SCK_38") (pintype "passive"))
      (node (ref "U6") (pin "83") (pinfunction "PH6_83") (pintype "passive"))
    )
    (net (code "125") (name "/PH7") (class "Default")
      (node (ref "LCD1") (pin "31") (pinfunction "T_PEN_31") (pintype "passive"))
      (node (ref "LCD2") (pin "39") (pinfunction "T_PEN_39") (pintype "passive"))
      (node (ref "U6") (pin "84") (pinfunction "PH7_84") (pintype "passive"))
    )
    (net (code "126") (name "/PH8") (class "Default")
      (node (ref "H6") (pin "3") (pinfunction "3_3") (pintype "passive"))
      (node (ref "U6") (pin "85") (pinfunction "PH8_85") (pintype "passive"))
    )
    (net (code "127") (name "/PH9") (class "Default")
      (node (ref "H6") (pin "4") (pinfunction "4_4") (pintype "passive"))
      (node (ref "LCD2") (pin "6") (pinfunction "R3_6") (pintype "passive"))
      (node (ref "U6") (pin "86") (pinfunction "PH9_86") (pintype "passive"))
    )
    (net (code "128") (name "/PH10") (class "Default")
      (node (ref "H6") (pin "5") (pinfunction "5_5") (pintype "passive"))
      (node (ref "LCD2") (pin "7") (pinfunction "R4_7") (pintype "passive"))
      (node (ref "U6") (pin "87") (pinfunction "PH10_87") (pintype "passive"))
    )
    (net (code "129") (name "/PH11") (class "Default")
      (node (ref "H6") (pin "6") (pinfunction "6_6") (pintype "passive"))
      (node (ref "LCD2") (pin "8") (pinfunction "R5_8") (pintype "passive"))
      (node (ref "U6") (pin "88") (pinfunction "PH11_88") (pintype "passive"))
    )
    (net (code "130") (name "/PH12") (class "Default")
      (node (ref "H6") (pin "8") (pinfunction "8_8") (pintype "passive"))
      (node (ref "LCD2") (pin "9") (pinfunction "R6_9") (pintype "passive"))
      (node (ref "U6") (pin "89") (pinfunction "PH12_89") (pintype "passive"))
    )
    (net (code "131") (name "/PH13") (class "Default")
      (node (ref "LCD2") (pin "14") (pinfunction "G2_14") (pintype "passive"))
      (node (ref "U6") (pin "128") (pinfunction "PH13_128") (pintype "passive"))
    )
    (net (code "132") (name "/PH14") (class "Default")
      (node (ref "LCD2") (pin "15") (pinfunction "G3_15") (pintype "passive"))
      (node (ref "U6") (pin "129") (pinfunction "PH14_129") (pintype "passive"))
    )
    (net (code "133") (name "/PH15") (class "Default")
      (node (ref "LCD2") (pin "16") (pinfunction "G4_16") (pintype "passive"))
      (node (ref "U6") (pin "130") (pinfunction "PH15_130") (pintype "passive"))
    )
    (net (code "134") (name "/PI0") (class "Default")
      (node (ref "LCD2") (pin "17") (pinfunction "G5_17") (pintype "passive"))
      (node (ref "U6") (pin "131") (pinfunction "PI0_131") (pintype "passive"))
    )
    (net (code "135") (name "/PI1") (class "Default")
      (node (ref "LCD2") (pin "18") (pinfunction "G6_18") (pintype "passive"))
      (node (ref "U6") (pin "132") (pinfunction "PI1_132") (pintype "passive"))
    )
    (net (code "136") (name "/PI2") (class "Default")
      (node (ref "LCD2") (pin "19") (pinfunction "G7_19") (pintype "passive"))
      (node (ref "U6") (pin "133") (pinfunction "PI2_133") (pintype "passive"))
    )
    (net (code "137") (name "/PI3") (class "Default")
      (node (ref "LCD1") (pin "30") (pinfunction "MOSI_30") (pintype "passive"))
      (node (ref "LCD2") (pin "36") (pinfunction "T_MOSI_36") (pintype "passive"))
      (node (ref "U6") (pin "134") (pinfunction "PI3_134") (pintype "passive"))
    )
    (net (code "138") (name "/PI4") (class "Default")
      (node (ref "LCD2") (pin "25") (pinfunction "B4_25") (pintype "passive"))
      (node (ref "U6") (pin "173") (pinfunction "PI4_173") (pintype "passive"))
    )
    (net (code "139") (name "/PI5") (class "Default")
      (node (ref "LCD2") (pin "26") (pinfunction "B5_26") (pintype "passive"))
      (node (ref "U6") (pin "174") (pinfunction "PI5_174") (pintype "passive"))
    )
    (net (code "140") (name "/PI6") (class "Default")
      (node (ref "LCD2") (pin "27") (pinfunction "B6_27") (pintype "passive"))
      (node (ref "U6") (pin "175") (pinfunction "PI6_175") (pintype "passive"))
    )
    (net (code "141") (name "/PI7") (class "Default")
      (node (ref "LCD2") (pin "28") (pinfunction "B7_28") (pintype "passive"))
      (node (ref "U6") (pin "176") (pinfunction "PI7_176") (pintype "passive"))
    )
    (net (code "142") (name "/PI8") (class "Default")
      (node (ref "LCD1") (pin "33") (pinfunction "T_CS_33") (pintype "passive"))
      (node (ref "LCD2") (pin "35") (pinfunction "T_CS_35") (pintype "passive"))
      (node (ref "U6") (pin "7") (pinfunction "PI8_7") (pintype "passive"))
    )
    (net (code "143") (name "/PI9") (class "Default")
      (node (ref "LCD2") (pin "32") (pinfunction "VSYNC_32") (pintype "passive"))
      (node (ref "U6") (pin "11") (pinfunction "PI9_11") (pintype "passive"))
    )
    (net (code "144") (name "/PI10") (class "Default")
      (node (ref "LCD2") (pin "31") (pinfunction "HSYNC_31") (pintype "passive"))
      (node (ref "U6") (pin "12") (pinfunction "PI10_12") (pintype "passive"))
    )
    (net (code "145") (name "/PI11") (class "Default")
      (node (ref "U5") (pin "24") (pinfunction "24_24") (pintype "passive"))
      (node (ref "U6") (pin "13") (pinfunction "PI11_13") (pintype "passive"))
    )
    (net (code "146") (name "<NO NET>") (class "Default")
      (node (ref "B1") (pin "2") (pinfunction "2_2") (pintype "passive"))
      (node (ref "C1") (pin "1") (pinfunction "1_1") (pintype "passive"))
      (node (ref "C10") (pin "1") (pinfunction "1_1") (pintype "passive"))
      (node (ref "C11") (pin "1") (pinfunction "1_1") (pintype "passive"))
      (node (ref "C12") (pin "1") (pinfunction "1_1") (pintype "passive"))
      (node (ref "C13") (pin "1") (pinfunction "1_1") (pintype "passive"))
      (node (ref "C14") (pin "1") (pinfunction "1_1") (pintype "passive"))
      (node (ref "C15") (pin "1") (pinfunction "1_1") (pintype "passive"))
      (node (ref "C16") (pin "1") (pinfunction "1_1") (pintype "passive"))
      (node (ref "C17") (pin "1") (pinfunction "1_1") (pintype "passive"))
      (node (ref "C18") (pin "1") (pinfunction "1_1") (pintype "passive"))
      (node (ref "C19") (pin "1") (pinfunction "1_1") (pintype "passive"))
      (node (ref "C2") (pin "1") (pinfunction "1_1") (pintype "passive"))
      (node (ref "C20") (pin "1") (pinfunction "1_1") (pintype "passive"))
      (node (ref "C21") (pin "1") (pinfunction "1_1") (pintype "passive"))
      (node (ref "C22") (pin "1") (pinfunction "1_1") (pintype "passive"))
      (node (ref "C23") (pin "1") (pinfunction "1_1") (pintype "passive"))
      (node (ref "C24") (pin "1") (pinfunction "1_1") (pintype "passive"))
      (node (ref "C25") (pin "1") (pinfunction "1_1") (pintype "passive"))
      (node (ref "C26") (pin "1") (pinfunction "1_1") (pintype "passive"))
      (node (ref "C27") (pin "1") (pinfunction "1_1") (pintype "passive"))
      (node (ref "C28") (pin "1") (pinfunction "1_1") (pintype "passive"))
      (node (ref "C29") (pin "1") (pinfunction "1_1") (pintype "passive"))
      (node (ref "C3") (pin "1") (pinfunction "1_1") (pintype "passive"))
      (node (ref "C30") (pin "1") (pinfunction "1_1") (pintype "passive"))
      (node (ref "C31") (pin "1") (pinfunction "1_1") (pintype "passive"))
      (node (ref "C32") (pin "2") (pinfunction "2_2") (pintype "passive"))
      (node (ref "C33") (pin "1") (pinfunction "1_1") (pintype "passive"))
      (node (ref "C34") (pin "2") (pinfunction "2_2") (pintype "passive"))
      (node (ref "C35") (pin "1") (pinfunction "1_1") (pintype "passive"))
      (node (ref "C36") (pin "1") (pinfunction "1_1") (pintype "passive"))
      (node (ref "C37") (pin "1") (pinfunction "1_1") (pintype "passive"))
      (node (ref "C38") (pin "1") (pinfunction "1_1") (pintype "passive"))
      (node (ref "C39") (pin "1") (pinfunction "1_1") (pintype "passive"))
      (node (ref "C4") (pin "1") (pinfunction "1_1") (pintype "passive"))
      (node (ref "C40") (pin "1") (pinfunction "1_1") (pintype "passive"))
      (node (ref "C41") (pin "1") (pinfunction "1_1") (pintype "passive"))
      (node (ref "C42") (pin "1") (pinfunction "1_1") (pintype "passive"))
      (node (ref "C43") (pin "1") (pinfunction "1_1") (pintype "passive"))
      (node (ref "C44") (pin "1") (pinfunction "1_1") (pintype "passive"))
      (node (ref "C5") (pin "1") (pinfunction "1_1") (pintype "passive"))
      (node (ref "C6") (pin "1") (pinfunction "1_1") (pintype "passive"))
      (node (ref "C7") (pin "1") (pinfunction "1_1") (pintype "passive"))
      (node (ref "C8") (pin "1") (pinfunction "1_1") (pintype "passive"))
      (node (ref "C9") (pin "1") (pinfunction "1_1") (pintype "passive"))
      (node (ref "D2") (pin "2") (pinfunction "GND_2") (pintype "passive"))
      (node (ref "H2") (pin "1") (pinfunction "1_1") (pintype "passive"))
      (node (ref "H2") (pin "3") (pinfunction "3_3") (pintype "passive"))
      (node (ref "H2") (pin "5") (pinfunction "5_5") (pintype "passive"))
      (node (ref "H2") (pin "7") (pinfunction "7_7") (pintype "passive"))
      (node (ref "H3") (pin "1") (pinfunction "1_1") (pintype "passive"))
      (node (ref "H3") (pin "3") (pinfunction "3_3") (pintype "passive"))
      (node (ref "H3") (pin "5") (pinfunction "5_5") (pintype "passive"))
      (node (ref "H3") (pin "7") (pinfunction "7_7") (pintype "passive"))
      (node (ref "H4") (pin "5") (pinfunction "5_5") (pintype "passive"))
      (node (ref "H4") (pin "6") (pinfunction "6_6") (pintype "passive"))
      (node (ref "JLINK") (pin "1") (pinfunction "1_1") (pintype "passive"))
      (node (ref "KEY") (pin "2") (pinfunction "2_2") (pintype "passive"))
      (node (ref "LCD1") (pin "22") (pinfunction "GND_22") (pintype "passive"))
      (node (ref "LCD1") (pin "26") (pinfunction "GND_26") (pintype "passive"))
      (node (ref "LCD1") (pin "27") (pinfunction "GND_27") (pintype "passive"))
      (node (ref "LCD2") (pin "11") (pinfunction "GND_11") (pintype "passive"))
      (node (ref "LCD2") (pin "12") (pinfunction "G0_12") (pintype "passive"))
      (node (ref "LCD2") (pin "13") (pinfunction "G1_13") (pintype "passive"))
      (node (ref "LCD2") (pin "20") (pinfunction "GND_20") (pintype "passive"))
      (node (ref "LCD2") (pin "21") (pinfunction "B0_21") (pintype "passive"))
      (node (ref "LCD2") (pin "22") (pinfunction "B1_22") (pintype "passive"))
      (node (ref "LCD2") (pin "23") (pinfunction "B2_23") (pintype "passive"))
      (node (ref "LCD2") (pin "29") (pinfunction "GND_29") (pintype "passive"))
      (node (ref "LCD2") (pin "3") (pinfunction "R0_3") (pintype "passive"))
      (node (ref "LCD2") (pin "4") (pinfunction "R1_4") (pintype "passive"))
      (node (ref "LCD2") (pin "41") (pinfunction "GND_3_41") (pintype "passive"))
      (node (ref "LCD2") (pin "42") (pinfunction "GND_4_42") (pintype "passive"))
      (node (ref "LCD2") (pin "5") (pinfunction "R2_5") (pintype "passive"))
      (node (ref "PWR") (pin "1") (pinfunction "-_1") (pintype "passive"))
      (node (ref "R14") (pin "2") (pinfunction "2_2") (pintype "passive"))
      (node (ref "R16") (pin "1") (pinfunction "1_1") (pintype "passive"))
      (node (ref "R17") (pin "2") (pinfunction "2_2") (pintype "passive"))
      (node (ref "R21") (pin "1") (pinfunction "1_1") (pintype "passive"))
      (node (ref "RESET") (pin "2") (pinfunction "2_2") (pintype "passive"))
      (node (ref "U1") (pin "23") (pinfunction "VSS1_23") (pintype "passive"))
      (node (ref "U1") (pin "35") (pinfunction "VSS2_35") (pintype "passive"))
      (node (ref "U1") (pin "44") (pinfunction "Boot0_44") (pintype "passive"))
      (node (ref "U1") (pin "47") (pinfunction "VSS3_47") (pintype "passive"))
      (node (ref "U1") (pin "8") (pinfunction "VSSA_8") (pintype "passive"))
      (node (ref "U2") (pin "1") (pinfunction "ADJ(GND)_1") (pintype "passive"))
      (node (ref "U3") (pin "12") (pinfunction "VSSQ_12") (pintype "passive"))
      (node (ref "U3") (pin "28") (pinfunction "VSS_28") (pintype "passive"))
      (node (ref "U3") (pin "41") (pinfunction "VSS_41") (pintype "passive"))
      (node (ref "U3") (pin "46") (pinfunction "VSSQ_46") (pintype "passive"))
      (node (ref "U3") (pin "52") (pinfunction "VSSQ_52") (pintype "passive"))
      (node (ref "U3") (pin "54") (pinfunction "VSS_54") (pintype "passive"))
      (node (ref "U3") (pin "6") (pinfunction "VSSQ_6") (pintype "passive"))
      (node (ref "U4") (pin "1") (pinfunction "A0_1") (pintype "passive"))
      (node (ref "U4") (pin "2") (pinfunction "A1_2") (pintype "passive"))
      (node (ref "U4") (pin "3") (pinfunction "A2_3") (pintype "passive"))
      (node (ref "U4") (pin "4") (pinfunction "GND_4") (pintype "passive"))
      (node (ref "U6") (pin "102") (pinfunction "VSS_102") (pintype "passive"))
      (node (ref "U6") (pin "113") (pinfunction "VSS_113") (pintype "passive"))
      (node (ref "U6") (pin "126") (pinfunction "VSS_126") (pintype "passive"))
      (node (ref "U6") (pin "135") (pinfunction "VSS_135") (pintype "passive"))
      (node (ref "U6") (pin "14") (pinfunction "VSS_14") (pintype "passive"))
      (node (ref "U6") (pin "148") (pinfunction "VSS_148") (pintype "passive"))
      (node (ref "U6") (pin "158") (pinfunction "VSS_158") (pintype "passive"))
      (node (ref "U6") (pin "22") (pinfunction "VSS_22") (pintype "passive"))
      (node (ref "U6") (pin "37") (pinfunction "VSSA_37") (pintype "passive"))
      (node (ref "U6") (pin "48") (pinfunction "BYPASS_REG_48") (pintype "passive"))
      (node (ref "U6") (pin "61") (pinfunction "VSS_61") (pintype "passive"))
      (node (ref "U6") (pin "71") (pinfunction "VSS_71") (pintype "passive"))
      (node (ref "U6") (pin "90") (pinfunction "VSS_90") (pintype "passive"))
      (node (ref "USB") (pin "1") (pinfunction "EP_1") (pintype "passive"))
      (node (ref "USB") (pin "2") (pinfunction "EP_2") (pintype "passive"))
      (node (ref "USB") (pin "3") (pinfunction "EP_3") (pintype "passive"))
      (node (ref "USB") (pin "4") (pinfunction "EP_4") (pintype "passive"))
      (node (ref "USB") (pin "A1") (pinfunction "GND_A1") (pintype "passive"))
      (node (ref "USB") (pin "A12") (pinfunction "GND_A12") (pintype "passive"))
      (node (ref "USB") (pin "B1") (pinfunction "GND_B1") (pintype "passive"))
      (node (ref "USB") (pin "B12") (pinfunction "GND_B12") (pintype "passive"))
      (node (ref "X1") (pin "2") (pinfunction "GND_2") (pintype "passive"))
      (node (ref "X1") (pin "4") (pinfunction "GND_4") (pintype "passive"))
    )
    (net (code "147") (name "Net-(D1-K)") (class "Default")
      (node (ref "C4") (pin "2") (pinfunction "2_2") (pintype "passive"))
      (node (ref "D1") (pin "3") (pinfunction "K_3") (pintype "passive"))
      (node (ref "U6") (pin "6") (pinfunction "VBAT_6") (pintype "passive"))
    )
    (net (code "148") (name "Net-(H1-Pad2)") (class "Default")
      (node (ref "H1") (pin "2") (pinfunction "2_2") (pintype "passive"))
      (node (ref "R3") (pin "2") (pinfunction "2_2") (pintype "passive"))
    )
    (net (code "149") (name "Net-(H1-Pad4)") (class "Default")
      (node (ref "H1") (pin "4") (pinfunction "4_4") (pintype "passive"))
      (node (ref "R4") (pin "2") (pinfunction "2_2") (pintype "passive"))
    )
    (net (code "150") (name "Net-(H1-Pad6)") (class "Default")
      (node (ref "H1") (pin "6") (pinfunction "6_6") (pintype "passive"))
      (node (ref "R5") (pin "2") (pinfunction "2_2") (pintype "passive"))
    )
    (net (code "151") (name "Net-(H1-Pad8)") (class "Default")
      (node (ref "H1") (pin "8") (pinfunction "8_8") (pintype "passive"))
      (node (ref "R7") (pin "1") (pinfunction "1_1") (pintype "passive"))
    )
    (net (code "152") (name "Net-(H1-Pad10)") (class "Default")
      (node (ref "H1") (pin "10") (pinfunction "10_10") (pintype "passive"))
      (node (ref "R6") (pin "1") (pinfunction "1_1") (pintype "passive"))
    )
    (net (code "153") (name "Net-(H4-Pad3)") (class "Default")
      (node (ref "H4") (pin "3") (pinfunction "3_3") (pintype "passive"))
      (node (ref "R9") (pin "1") (pinfunction "1_1") (pintype "passive"))
    )
    (net (code "154") (name "Net-(H4-Pad4)") (class "Default")
      (node (ref "H4") (pin "4") (pinfunction "4_4") (pintype "passive"))
      (node (ref "R10") (pin "2") (pinfunction "2_2") (pintype "passive"))
    )
    (net (code "155") (name "Net-(H5-Pad5)") (class "Default")
      (node (ref "H5") (pin "5") (pinfunction "5_5") (pintype "passive"))
      (node (ref "KEY") (pin "1") (pinfunction "1_1") (pintype "passive"))
      (node (ref "R15") (pin "1") (pinfunction "1_1") (pintype "passive"))
    )
    (net (code "156") (name "Net-(H5-Pad7)") (class "Default")
      (node (ref "H5") (pin "7") (pinfunction "7_7") (pintype "passive"))
      (node (ref "WK_UP") (pin "2") (pinfunction "2_2") (pintype "passive"))
    )
    (net (code "157") (name "Net-(LED1-+)") (class "Default")
      (node (ref "LED1") (pin "2") (pinfunction "+_2") (pintype "passive"))
      (node (ref "R12") (pin "2") (pinfunction "2_2") (pintype "passive"))
    )
    (net (code "158") (name "Net-(LED1--)") (class "Default")
      (node (ref "H5") (pin "1") (pinfunction "1_1") (pintype "passive"))
      (node (ref "LED1") (pin "1") (pinfunction "-_1") (pintype "passive"))
    )
    (net (code "159") (name "Net-(LED2-+)") (class "Default")
      (node (ref "LED2") (pin "2") (pinfunction "+_2") (pintype "passive"))
      (node (ref "R13") (pin "2") (pinfunction "2_2") (pintype "passive"))
    )
    (net (code "160") (name "Net-(LED2--)") (class "Default")
      (node (ref "H5") (pin "3") (pinfunction "3_3") (pintype "passive"))
      (node (ref "LED2") (pin "1") (pinfunction "-_1") (pintype "passive"))
    )
    (net (code "161") (name "Net-(LINK-+)") (class "Default")
      (node (ref "LINK") (pin "2") (pinfunction "+_2") (pintype "passive"))
      (node (ref "R1") (pin "1") (pinfunction "1_1") (pintype "passive"))
    )
    (net (code "162") (name "Net-(LINK--)") (class "Default")
      (node (ref "LINK") (pin "1") (pinfunction "-_1") (pintype "passive"))
      (node (ref "U1") (pin "10") (pinfunction "PA0_10") (pintype "passive"))
    )
    (net (code "163") (name "Net-(PWR-+)") (class "Default")
      (node (ref "PWR") (pin "2") (pinfunction "+_2") (pintype "passive"))
      (node (ref "R11") (pin "1") (pinfunction "1_1") (pintype "passive"))
    )
    (net (code "164") (name "Net-(U1-NRST)") (class "Default")
      (node (ref "C5") (pin "2") (pinfunction "2_2") (pintype "passive"))
      (node (ref "R2") (pin "1") (pinfunction "1_1") (pintype "passive"))
      (node (ref "U1") (pin "7") (pinfunction "NRST_7") (pintype "passive"))
    )
    (net (code "165") (name "Net-(U1-PA1)") (class "Default")
      (node (ref "R3") (pin "1") (pinfunction "1_1") (pintype "passive"))
      (node (ref "U1") (pin "11") (pinfunction "PA1_11") (pintype "passive"))
    )
    (net (code "166") (name "Net-(U1-PA2)") (class "Default")
      (node (ref "R4") (pin "1") (pinfunction "1_1") (pintype "passive"))
      (node (ref "U1") (pin "12") (pinfunction "PA2_12") (pintype "passive"))
    )
    (net (code "167") (name "Net-(U1-PA4)") (class "Default")
      (node (ref "R5") (pin "1") (pinfunction "1_1") (pintype "passive"))
      (node (ref "U1") (pin "14") (pinfunction "PA4_14") (pintype "passive"))
    )
    (net (code "168") (name "Net-(U1-PA9)") (class "Default")
      (node (ref "R7") (pin "2") (pinfunction "2_2") (pintype "passive"))
      (node (ref "U1") (pin "30") (pinfunction "PA9_30") (pintype "passive"))
    )
    (net (code "169") (name "Net-(U1-PA10)") (class "Default")
      (node (ref "R6") (pin "2") (pinfunction "2_2") (pintype "passive"))
      (node (ref "U1") (pin "31") (pinfunction "PA10_31") (pintype "passive"))
    )
    (net (code "170") (name "Net-(U1-PA13)") (class "Default")
      (node (ref "JLINK") (pin "3") (pinfunction "3_3") (pintype "passive"))
      (node (ref "U1") (pin "34") (pinfunction "PA13_34") (pintype "passive"))
    )
    (net (code "171") (name "Net-(U1-PA14)") (class "Default")
      (node (ref "JLINK") (pin "2") (pinfunction "2_2") (pintype "passive"))
      (node (ref "U1") (pin "37") (pinfunction "PA14_37") (pintype "passive"))
    )
    (net (code "172") (name "Net-(U4-WP)") (class "Default")
      (node (ref "R19") (pin "2") (pinfunction "2_2") (pintype "passive"))
      (node (ref "R21") (pin "2") (pinfunction "2_2") (pintype "passive"))
      (node (ref "U4") (pin "7") (pinfunction "WP_7") (pintype "passive"))
    )
    (net (code "173") (name "Net-(U6A-PC14-OSC32_IN(PC14))") (class "Default")
      (node (ref "C29") (pin "2") (pinfunction "2_2") (pintype "passive"))
      (node (ref "U6") (pin "9") (pinfunction "PC14-OSC32_IN(PC14)_9") (pintype "passive"))
      (node (ref "X2") (pin "2") (pinfunction "2_2") (pintype "passive"))
    )
    (net (code "174") (name "Net-(U6A-PC15-OSC32_OUT(PC15))") (class "Default")
      (node (ref "C28") (pin "2") (pinfunction "2_2") (pintype "passive"))
      (node (ref "U6") (pin "10") (pinfunction "PC15-OSC32_OUT(PC15)_10") (pintype "passive"))
      (node (ref "X2") (pin "1") (pinfunction "1_1") (pintype "passive"))
    )
    (net (code "175") (name "Net-(U6B-PH0-OSC_IN(PH0))") (class "Default")
      (node (ref "C2") (pin "2") (pinfunction "2_2") (pintype "passive"))
      (node (ref "U6") (pin "29") (pinfunction "PH0-OSC_IN(PH0)_29") (pintype "passive"))
      (node (ref "X1") (pin "3") (pinfunction "OSC2_3") (pintype "passive"))
    )
    (net (code "176") (name "Net-(U6B-PH1-OSC_OUT(PH1))") (class "Default")
      (node (ref "C1") (pin "2") (pinfunction "2_2") (pintype "passive"))
      (node (ref "U6") (pin "30") (pinfunction "PH1-OSC_OUT(PH1)_30") (pintype "passive"))
      (node (ref "X1") (pin "1") (pinfunction "OSC1_1") (pintype "passive"))
    )
    (net (code "177") (name "Net-(U6B-VCAP_1)") (class "Default")
      (node (ref "C27") (pin "2") (pinfunction "2_2") (pintype "passive"))
      (node (ref "U6") (pin "81") (pinfunction "VCAP_1_81") (pintype "passive"))
    )
    (net (code "178") (name "Net-(U6B-VCAP_2)") (class "Default")
      (node (ref "C30") (pin "2") (pinfunction "2_2") (pintype "passive"))
      (node (ref "U6") (pin "125") (pinfunction "VCAP_2_125") (pintype "passive"))
    )
    (net (code "179") (name "Net-(U6C-VDDA)") (class "Default")
      (node (ref "C3") (pin "2") (pinfunction "2_2") (pintype "passive"))
      (node (ref "C6") (pin "2") (pinfunction "2_2") (pintype "passive"))
      (node (ref "L1") (pin "1") (pinfunction "1_1") (pintype "passive"))
      (node (ref "U6") (pin "38") (pinfunction "VREF+_38") (pintype "passive"))
      (node (ref "U6") (pin "39") (pinfunction "VDDA_39") (pintype "passive"))
    )
    (net (code "180") (name "Net-(USB-CC1)") (class "Default")
      (node (ref "R14") (pin "1") (pinfunction "1_1") (pintype "passive"))
      (node (ref "USB") (pin "A5") (pinfunction "CC1_A5") (pintype "passive"))
    )
    (net (code "181") (name "Net-(USB-CC2)") (class "Default")
      (node (ref "R16") (pin "2") (pinfunction "2_2") (pintype "passive"))
      (node (ref "USB") (pin "B5") (pinfunction "CC2_B5") (pintype "passive"))
    )
    (net (code "182") (name "VBAT") (class "Default")
      (node (ref "B1") (pin "1") (pinfunction "1_1") (pintype "passive"))
      (node (ref "D1") (pin "2") (pinfunction "A2_2") (pintype "passive"))
    )
    (net (code "183") (name "unconnected-(LCD1-MO-Pad32)") (class "Default")
      (node (ref "LCD1") (pin "32") (pinfunction "MO_32") (pintype "passive+no_connect"))
    )
    (net (code "184") (name "unconnected-(POWER-Pad1)") (class "Default")
      (node (ref "POWER") (pin "1") (pinfunction "1_1") (pintype "passive+no_connect"))
    )
    (net (code "185") (name "unconnected-(POWER-Pad6)") (class "Default")
      (node (ref "POWER") (pin "6") (pinfunction "6_6") (pintype "passive+no_connect"))
    )
    (net (code "186") (name "unconnected-(U1-OSC_I-Pad5)") (class "Default")
      (node (ref "U1") (pin "5") (pinfunction "OSC_I_5") (pintype "passive+no_connect"))
    )
    (net (code "187") (name "unconnected-(U1-OSC_O-Pad6)") (class "Default")
      (node (ref "U1") (pin "6") (pinfunction "OSC_O_6") (pintype "passive+no_connect"))
    )
    (net (code "188") (name "unconnected-(U1-PA3-Pad13)") (class "Default")
      (node (ref "U1") (pin "13") (pinfunction "PA3_13") (pintype "passive+no_connect"))
    )
    (net (code "189") (name "unconnected-(U1-PA5-Pad15)") (class "Default")
      (node (ref "U1") (pin "15") (pinfunction "PA5_15") (pintype "passive+no_connect"))
    )
    (net (code "190") (name "unconnected-(U1-PA6-Pad16)") (class "Default")
      (node (ref "U1") (pin "16") (pinfunction "PA6_16") (pintype "passive+no_connect"))
    )
    (net (code "191") (name "unconnected-(U1-PA7-Pad17)") (class "Default")
      (node (ref "U1") (pin "17") (pinfunction "PA7_17") (pintype "passive+no_connect"))
    )
    (net (code "192") (name "unconnected-(U1-PA8-Pad29)") (class "Default")
      (node (ref "U1") (pin "29") (pinfunction "PA8_29") (pintype "passive+no_connect"))
    )
    (net (code "193") (name "unconnected-(U1-PA15-Pad38)") (class "Default")
      (node (ref "U1") (pin "38") (pinfunction "PA15_38") (pintype "passive+no_connect"))
    )
    (net (code "194") (name "unconnected-(U1-PB0-Pad18)") (class "Default")
      (node (ref "U1") (pin "18") (pinfunction "PB0_18") (pintype "passive+no_connect"))
    )
    (net (code "195") (name "unconnected-(U1-PB1-Pad19)") (class "Default")
      (node (ref "U1") (pin "19") (pinfunction "PB1_19") (pintype "passive+no_connect"))
    )
    (net (code "196") (name "unconnected-(U1-PB2-Pad20)") (class "Default")
      (node (ref "U1") (pin "20") (pinfunction "PB2_20") (pintype "passive+no_connect"))
    )
    (net (code "197") (name "unconnected-(U1-PB3-Pad39)") (class "Default")
      (node (ref "U1") (pin "39") (pinfunction "PB3_39") (pintype "passive+no_connect"))
    )
    (net (code "198") (name "unconnected-(U1-PB4-Pad40)") (class "Default")
      (node (ref "U1") (pin "40") (pinfunction "PB4_40") (pintype "passive+no_connect"))
    )
    (net (code "199") (name "unconnected-(U1-PB5-Pad41)") (class "Default")
      (node (ref "U1") (pin "41") (pinfunction "PB5_41") (pintype "passive+no_connect"))
    )
    (net (code "200") (name "unconnected-(U1-PB6-Pad42)") (class "Default")
      (node (ref "U1") (pin "42") (pinfunction "PB6_42") (pintype "passive+no_connect"))
    )
    (net (code "201") (name "unconnected-(U1-PB7-Pad43)") (class "Default")
      (node (ref "U1") (pin "43") (pinfunction "PB7_43") (pintype "passive+no_connect"))
    )
    (net (code "202") (name "unconnected-(U1-PB8-Pad45)") (class "Default")
      (node (ref "U1") (pin "45") (pinfunction "PB8_45") (pintype "passive+no_connect"))
    )
    (net (code "203") (name "unconnected-(U1-PB9-Pad46)") (class "Default")
      (node (ref "U1") (pin "46") (pinfunction "PB9_46") (pintype "passive+no_connect"))
    )
    (net (code "204") (name "unconnected-(U1-PB10-Pad21)") (class "Default")
      (node (ref "U1") (pin "21") (pinfunction "PB10_21") (pintype "passive+no_connect"))
    )
    (net (code "205") (name "unconnected-(U1-PB11-Pad22)") (class "Default")
      (node (ref "U1") (pin "22") (pinfunction "PB11_22") (pintype "passive+no_connect"))
    )
    (net (code "206") (name "unconnected-(U1-PB12-Pad25)") (class "Default")
      (node (ref "U1") (pin "25") (pinfunction "PB12_25") (pintype "passive+no_connect"))
    )
    (net (code "207") (name "unconnected-(U1-PB13-Pad26)") (class "Default")
      (node (ref "U1") (pin "26") (pinfunction "PB13_26") (pintype "passive+no_connect"))
    )
    (net (code "208") (name "unconnected-(U1-PB14-Pad27)") (class "Default")
      (node (ref "U1") (pin "27") (pinfunction "PB14_27") (pintype "passive+no_connect"))
    )
    (net (code "209") (name "unconnected-(U1-PB15-Pad28)") (class "Default")
      (node (ref "U1") (pin "28") (pinfunction "PB15_28") (pintype "passive+no_connect"))
    )
    (net (code "210") (name "unconnected-(U1-PC13-Pad2)") (class "Default")
      (node (ref "U1") (pin "2") (pinfunction "PC13_2") (pintype "passive+no_connect"))
    )
    (net (code "211") (name "unconnected-(U1-PC14-Pad3)") (class "Default")
      (node (ref "U1") (pin "3") (pinfunction "PC14_3") (pintype "passive+no_connect"))
    )
    (net (code "212") (name "unconnected-(U1-PC15-Pad4)") (class "Default")
      (node (ref "U1") (pin "4") (pinfunction "PC15_4") (pintype "passive+no_connect"))
    )
    (net (code "213") (name "unconnected-(U3-NC-Pad40)") (class "Default")
      (node (ref "U3") (pin "40") (pinfunction "NC_40") (pintype "passive+no_connect"))
    )
    (net (code "214") (name "unconnected-(USB-SUB1-PadA8)") (class "Default")
      (node (ref "USB") (pin "A8") (pinfunction "SUB1_A8") (pintype "passive+no_connect"))
    )
    (net (code "215") (name "unconnected-(USB-SUB2-PadB8)") (class "Default")
      (node (ref "USB") (pin "B8") (pinfunction "SUB2_B8") (pintype "passive+no_connect"))
    )
  )
)
